# io-board-b-c.net
KiCad netlist of a schematic drawn in EAGLE
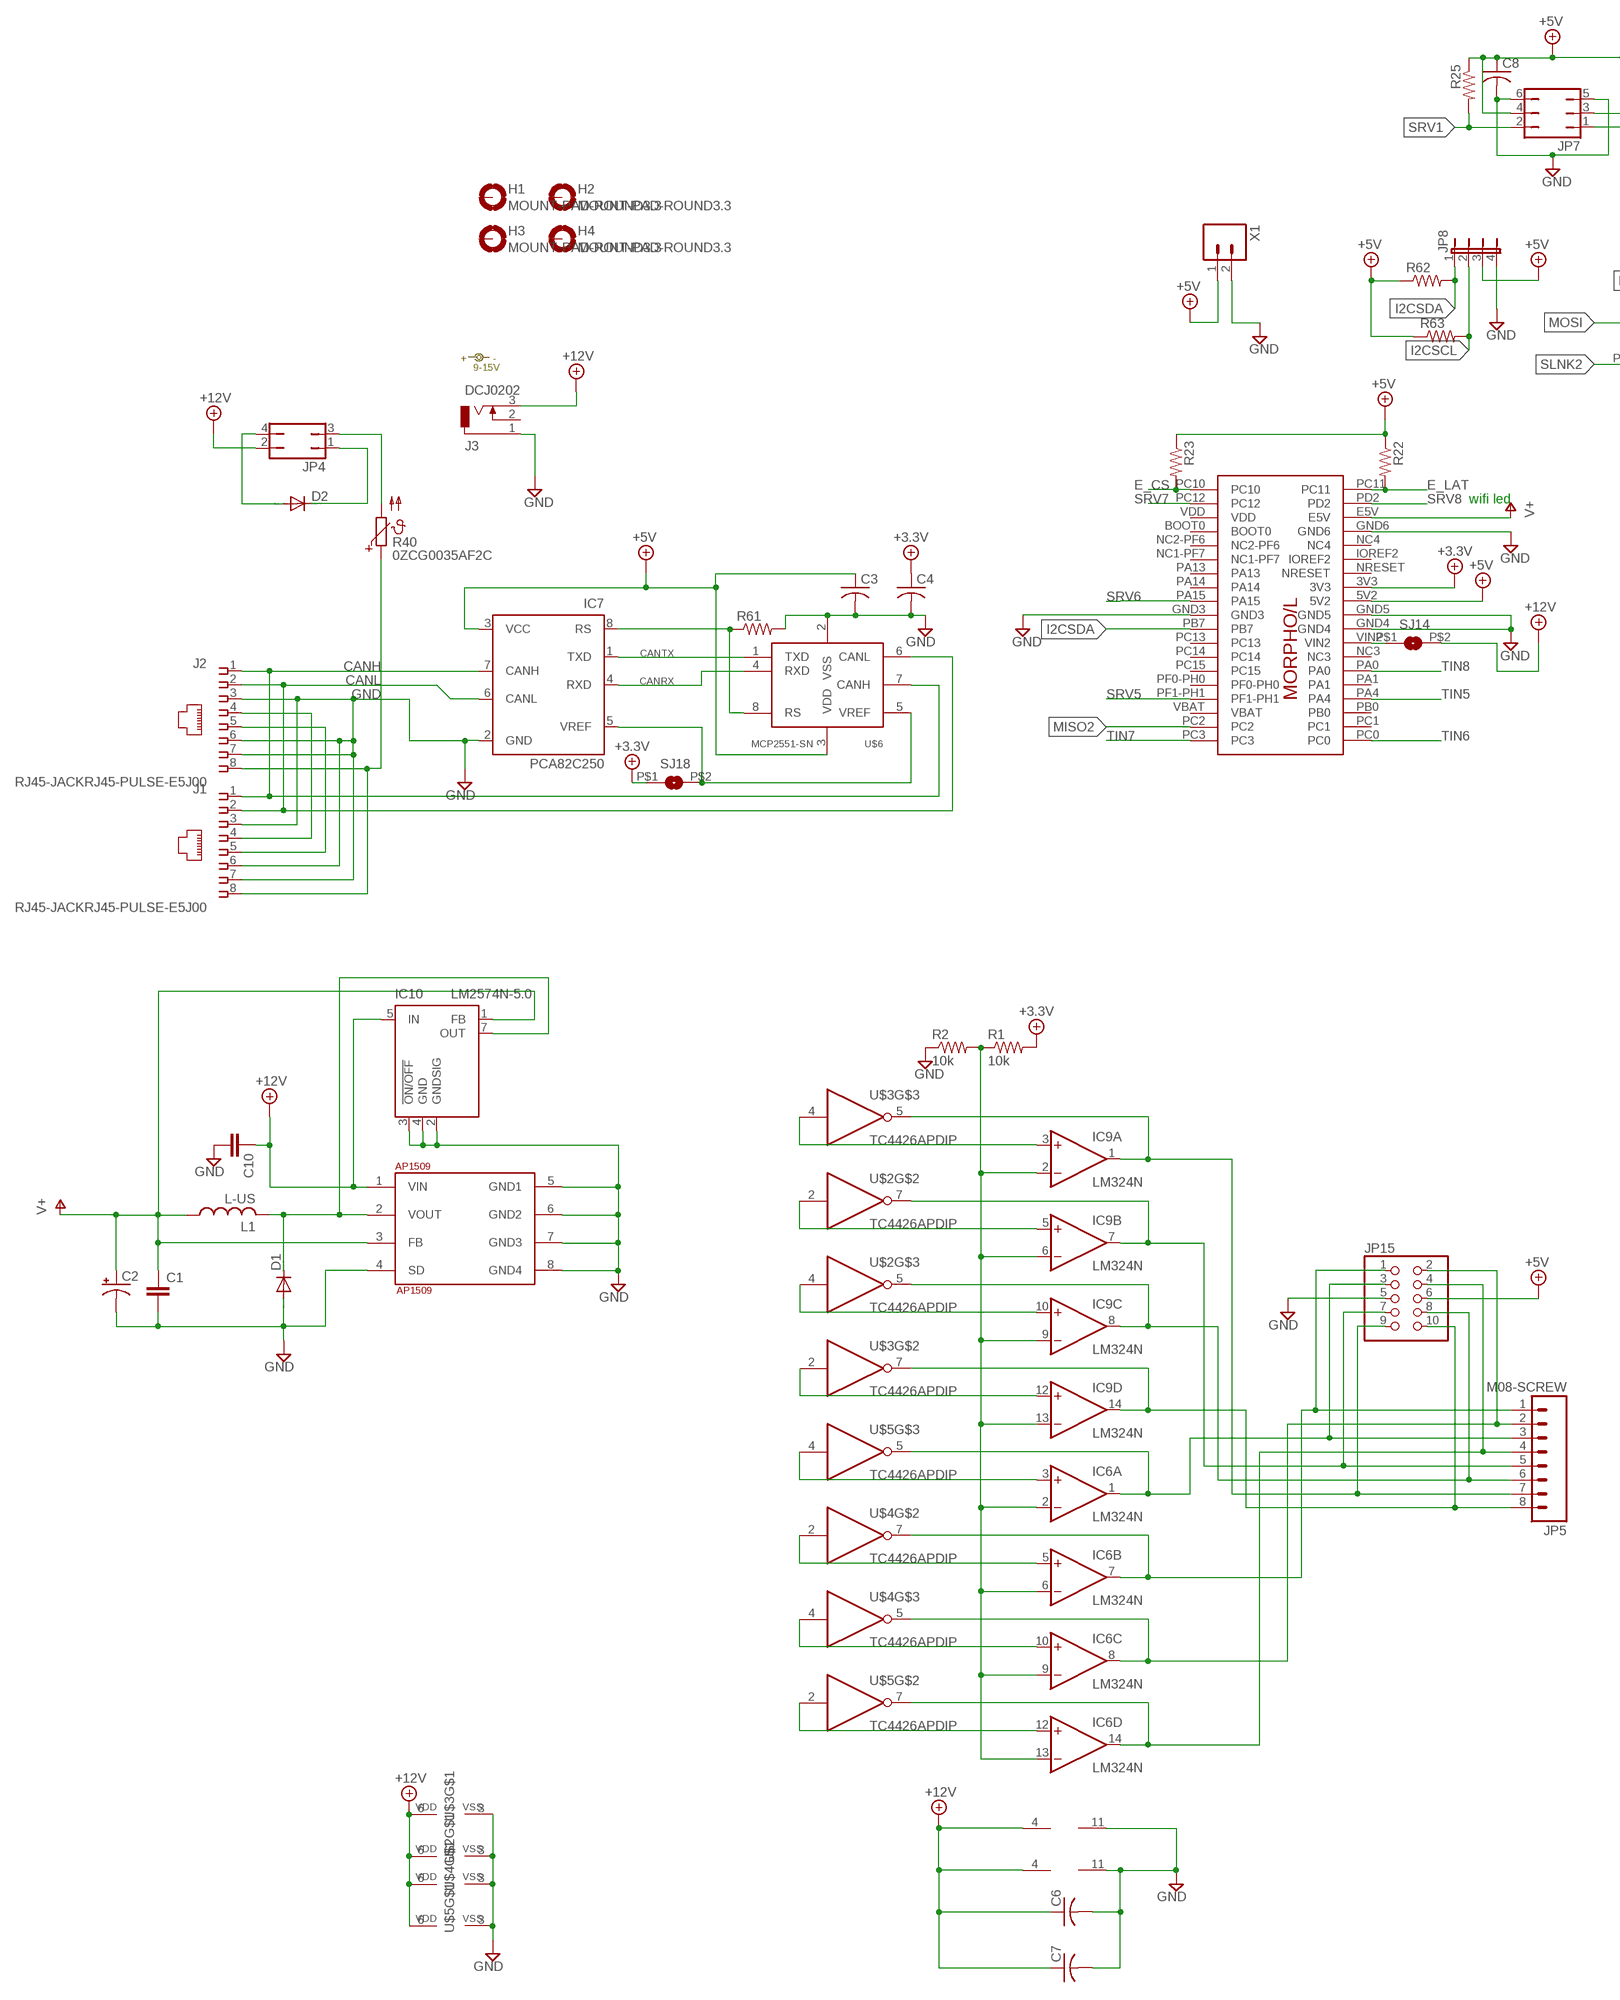
[diagram p0: schematic, sheet 1, part 1 of 2]
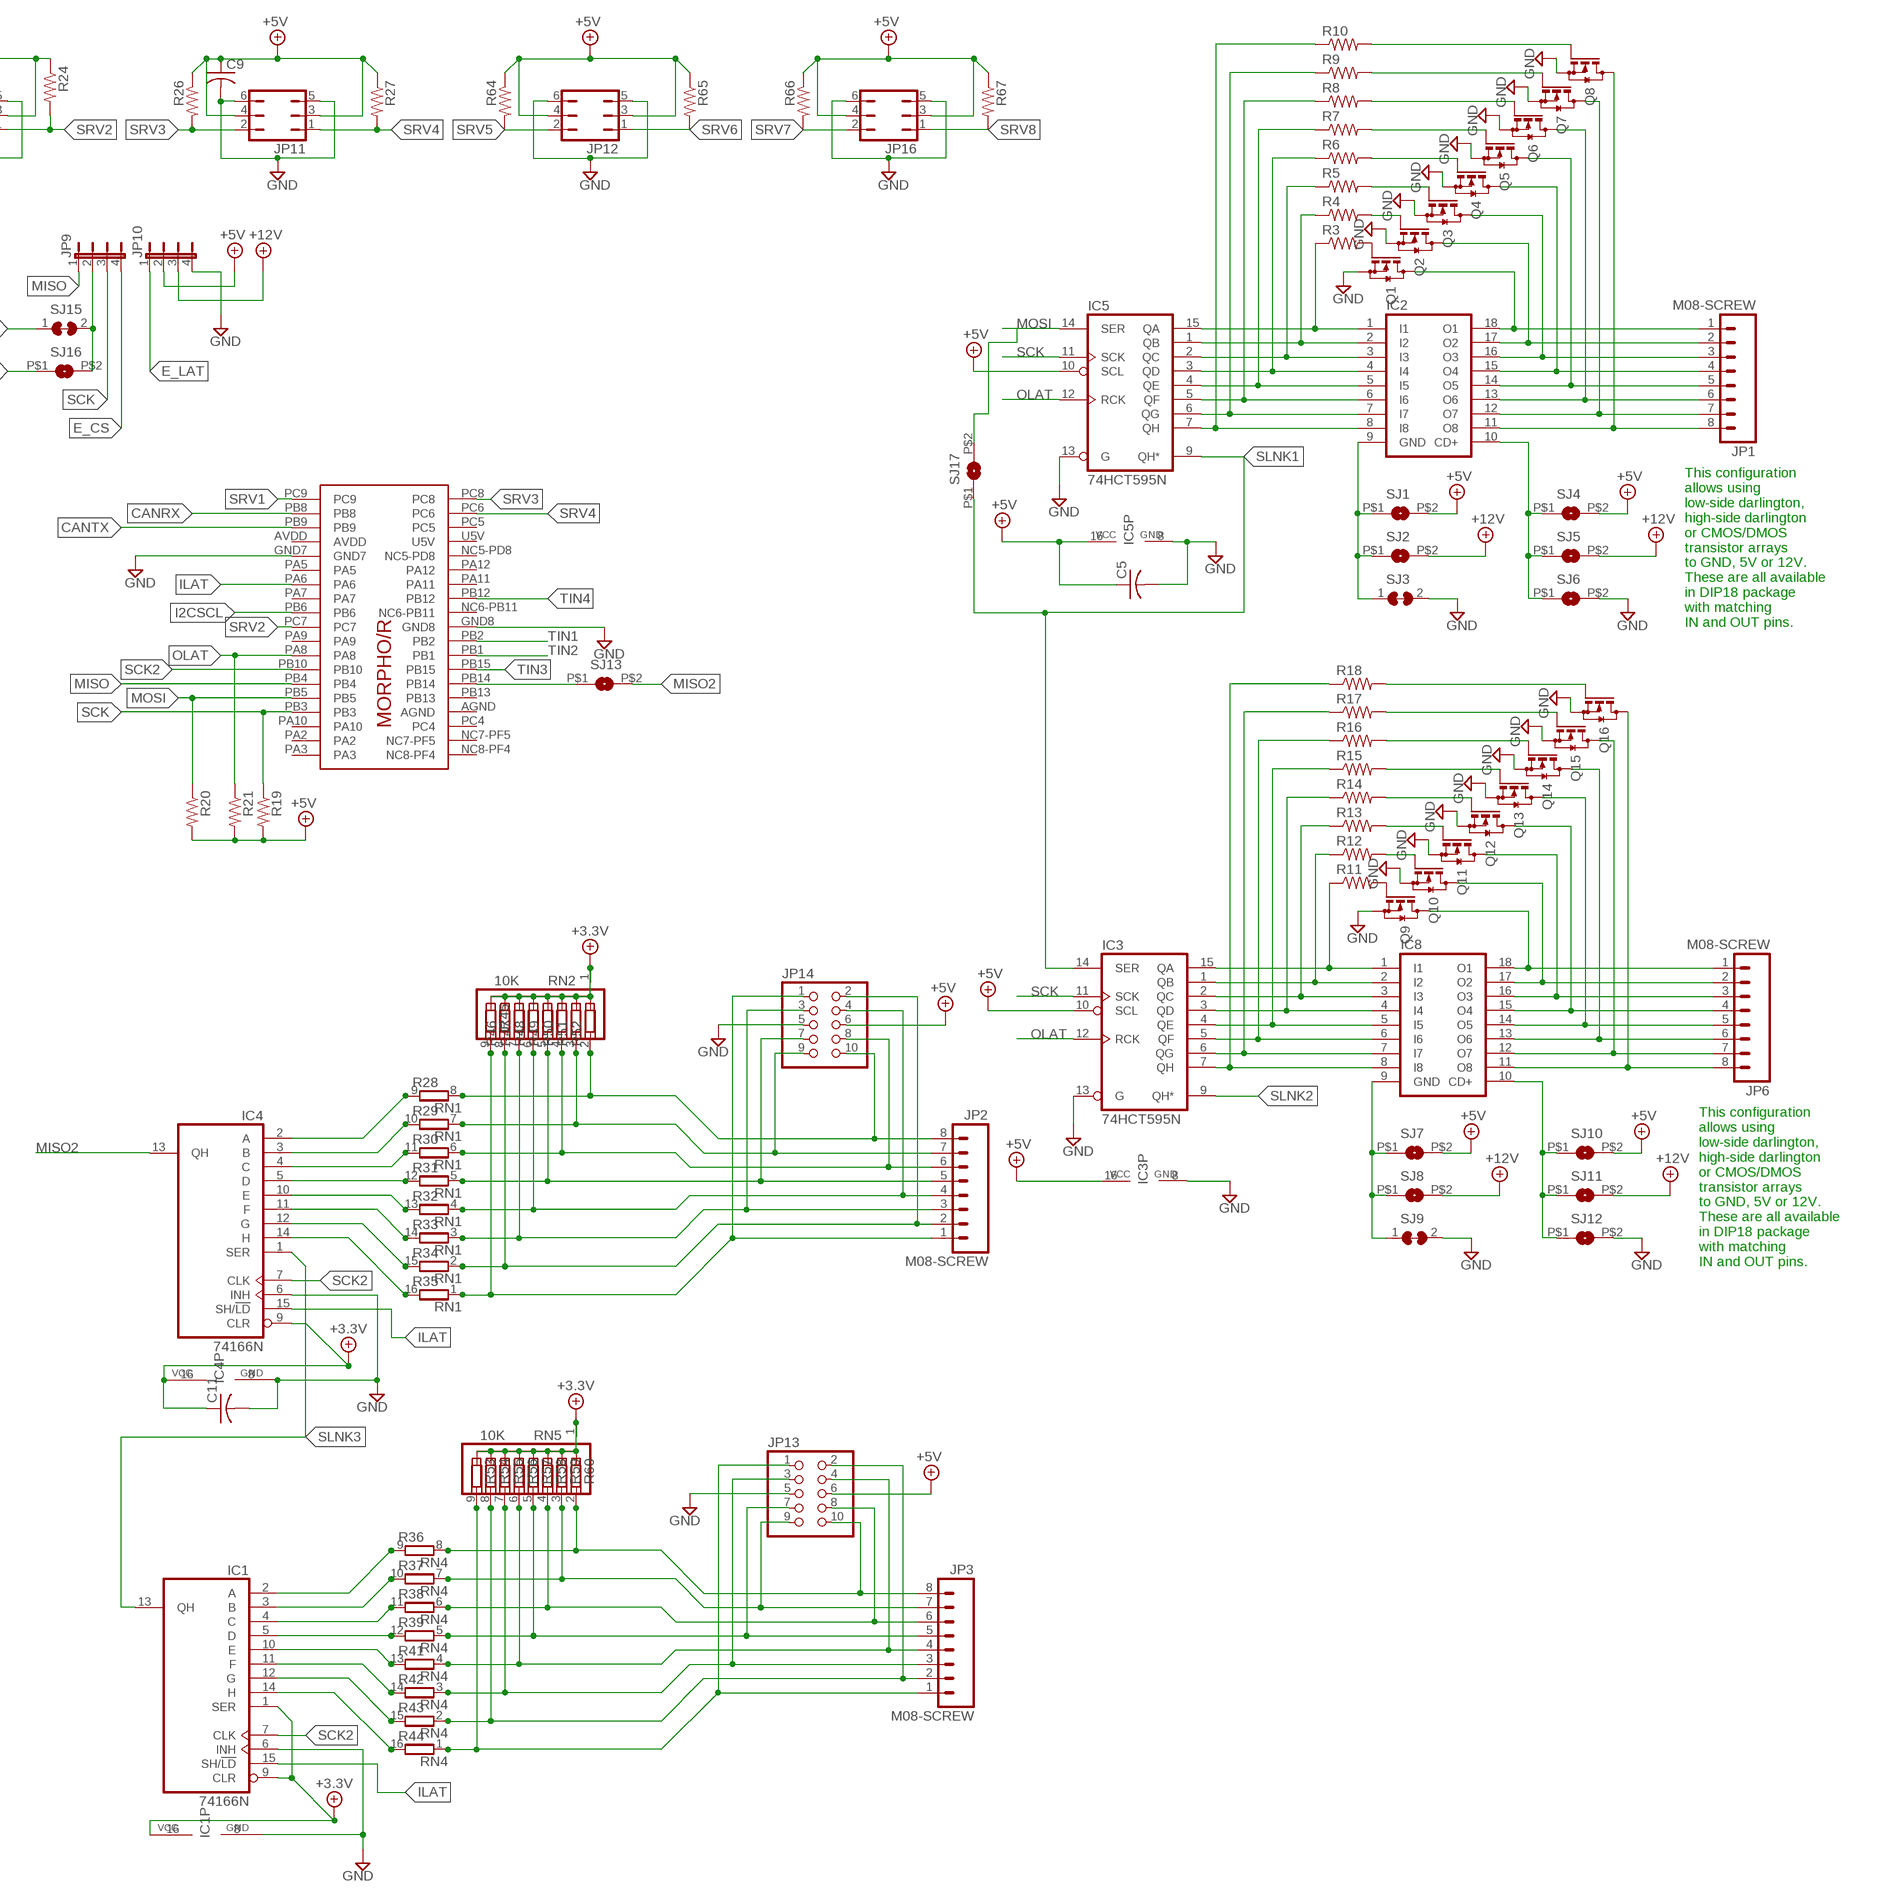
[diagram p1: schematic, sheet 1, part 2 of 2]

(export (version "E")
  (design (tool "Eeschema 10.0.6"))
  (components
    (comp (ref "+12V")
      (value "9-15V")
      (footprint "eagle-import:POWER_USAGE")
      (libsource (lib "eagle-import") (part "DOC-POWER_LABEL"))
    )
    (comp (ref "AP1509")
      (value "AP1509")
      (footprint "eagle-import:SO-08")
      (libsource (lib "eagle-import") (part "AP1509"))
    )
    (comp (ref "C1")
      (value "C-EUC1206")
      (footprint "eagle-import:C1206")
      (libsource (lib "eagle-import") (part "C-EUC1206"))
    )
    (comp (ref "C2")
      (value "CPOL-USE2.5-5")
      (footprint "eagle-import:E2,5-5")
      (libsource (lib "eagle-import") (part "CPOL-USE2.5-5"))
    )
    (comp (ref "C3")
      (value "C-USC0805")
      (footprint "eagle-import:C0805")
      (libsource (lib "eagle-import") (part "C-USC0805"))
    )
    (comp (ref "C4")
      (value "C-USC0805")
      (footprint "eagle-import:C0805")
      (libsource (lib "eagle-import") (part "C-USC0805"))
    )
    (comp (ref "C5")
      (value "C-USC0805")
      (footprint "eagle-import:C0805")
      (libsource (lib "eagle-import") (part "C-USC0805"))
    )
    (comp (ref "C6")
      (value "C-USC1206")
      (footprint "eagle-import:C1206")
      (libsource (lib "eagle-import") (part "C-USC1206"))
    )
    (comp (ref "C7")
      (value "C-USC1206")
      (footprint "eagle-import:C1206")
      (libsource (lib "eagle-import") (part "C-USC1206"))
    )
    (comp (ref "C8")
      (value "C-USC1206")
      (footprint "eagle-import:C1206")
      (libsource (lib "eagle-import") (part "C-USC1206"))
    )
    (comp (ref "C9")
      (value "C-USC1206")
      (footprint "eagle-import:C1206")
      (libsource (lib "eagle-import") (part "C-USC1206"))
    )
    (comp (ref "C10")
      (value "C-EUC1206")
      (footprint "eagle-import:C1206")
      (libsource (lib "eagle-import") (part "C-EUC1206"))
    )
    (comp (ref "C11")
      (value "C-USC0805")
      (footprint "eagle-import:C0805")
      (libsource (lib "eagle-import") (part "C-USC0805"))
    )
    (comp (ref "D1")
      (value "DIODE-DO41-7.6")
      (footprint "eagle-import:DO41-7.6")
      (libsource (lib "eagle-import") (part "DIODE-DO41-7.6"))
    )
    (comp (ref "D2")
      (value "DIODE-DO41-7.6")
      (footprint "eagle-import:DO41-7.6")
      (libsource (lib "eagle-import") (part "DIODE-DO41-7.6"))
    )
    (comp (ref "H1")
      (value "MOUNT-PAD-ROUND3.3")
      (footprint "eagle-import:3,3-PAD")
      (libsource (lib "eagle-import") (part "MOUNT-PAD-ROUND3.3"))
    )
    (comp (ref "H2")
      (value "MOUNT-PAD-ROUND3.3")
      (footprint "eagle-import:3,3-PAD")
      (libsource (lib "eagle-import") (part "MOUNT-PAD-ROUND3.3"))
    )
    (comp (ref "H3")
      (value "MOUNT-PAD-ROUND3.3")
      (footprint "eagle-import:3,3-PAD")
      (libsource (lib "eagle-import") (part "MOUNT-PAD-ROUND3.3"))
    )
    (comp (ref "H4")
      (value "MOUNT-PAD-ROUND3.3")
      (footprint "eagle-import:3,3-PAD")
      (libsource (lib "eagle-import") (part "MOUNT-PAD-ROUND3.3"))
    )
    (comp (ref "IC1")
      (value "74166N")
      (footprint "eagle-import:DIL16")
      (libsource (lib "eagle-import") (part "74166N"))
    )
    (comp (ref "IC2")
      (value "ULN2803A")
      (footprint "eagle-import:DIL18-THIN")
      (libsource (lib "eagle-import") (part "ULN2803A"))
    )
    (comp (ref "IC3")
      (value "74HCT595N")
      (footprint "eagle-import:DIL16")
      (libsource (lib "eagle-import") (part "74595NHCT"))
    )
    (comp (ref "IC4")
      (value "74166N")
      (footprint "eagle-import:DIL16")
      (libsource (lib "eagle-import") (part "74166N"))
    )
    (comp (ref "IC5")
      (value "74HCT595N")
      (footprint "eagle-import:DIL16")
      (libsource (lib "eagle-import") (part "74595NHCT"))
    )
    (comp (ref "IC6")
      (value "LM324N")
      (footprint "eagle-import:DIL14")
      (libsource (lib "eagle-import") (part "LM324N"))
    )
    (comp (ref "IC7")
      (value "PCA82C250")
      (footprint "eagle-import:DIL08")
      (libsource (lib "eagle-import") (part "PCA82C250"))
    )
    (comp (ref "IC8")
      (value "ULN2803A")
      (footprint "eagle-import:DIL18-THIN")
      (libsource (lib "eagle-import") (part "ULN2803A"))
    )
    (comp (ref "IC9")
      (value "LM324N")
      (footprint "eagle-import:DIL14")
      (libsource (lib "eagle-import") (part "LM324N"))
    )
    (comp (ref "IC10")
      (value "LM2574N-5.0")
      (footprint "eagle-import:DIL08")
      (libsource (lib "eagle-import") (part "LM2574?-N5.0"))
    )
    (comp (ref "J1")
      (value "RJ45-JACKRJ45-PULSE-E5J00")
      (footprint "eagle-import:RJ45-PULSE-E5J88")
      (libsource (lib "eagle-import") (part "RJ45-JACKRJ45-PULSE-E5J00"))
    )
    (comp (ref "J2")
      (value "RJ45-JACKRJ45-PULSE-E5J00")
      (footprint "eagle-import:RJ45-PULSE-E5J88")
      (libsource (lib "eagle-import") (part "RJ45-JACKRJ45-PULSE-E5J00"))
    )
    (comp (ref "J3")
      (value "DCJ0202")
      (footprint "eagle-import:DCJ0202")
      (libsource (lib "eagle-import") (part "DCJ0202"))
    )
    (comp (ref "JP1")
      (value "M08-SCREW")
      (footprint "eagle-import:1X08_TERMINAL")
      (libsource (lib "eagle-import") (part "M08-SCREW"))
    )
    (comp (ref "JP2")
      (value "M08-SCREW")
      (footprint "eagle-import:1X08_TERMINAL")
      (libsource (lib "eagle-import") (part "M08-SCREW"))
    )
    (comp (ref "JP3")
      (value "M08-SCREW")
      (footprint "eagle-import:1X08_TERMINAL")
      (libsource (lib "eagle-import") (part "M08-SCREW"))
    )
    (comp (ref "JP4")
      (value "JP2Q")
      (footprint "eagle-import:JP2Q")
      (libsource (lib "eagle-import") (part "JP2Q"))
    )
    (comp (ref "JP5")
      (value "M08-SCREW")
      (footprint "eagle-import:1X08_TERMINAL")
      (libsource (lib "eagle-import") (part "M08-SCREW"))
    )
    (comp (ref "JP6")
      (value "M08-SCREW")
      (footprint "eagle-import:1X08_TERMINAL")
      (libsource (lib "eagle-import") (part "M08-SCREW"))
    )
    (comp (ref "JP7")
      (value "JP3Q")
      (footprint "eagle-import:JP3Q")
      (libsource (lib "eagle-import") (part "JP3Q"))
    )
    (comp (ref "JP8")
      (value "JP4-FLAT")
      (footprint "eagle-import:JP4F")
      (libsource (lib "eagle-import") (part "JP4-FLAT"))
    )
    (comp (ref "JP9")
      (value "JP4-FLAT")
      (footprint "eagle-import:JP4F")
      (libsource (lib "eagle-import") (part "JP4-FLAT"))
    )
    (comp (ref "JP10")
      (value "JP4-FLAT")
      (footprint "eagle-import:JP4F")
      (libsource (lib "eagle-import") (part "JP4-FLAT"))
    )
    (comp (ref "JP11")
      (value "JP3Q")
      (footprint "eagle-import:JP3Q")
      (libsource (lib "eagle-import") (part "JP3Q"))
    )
    (comp (ref "JP12")
      (value "JP3Q")
      (footprint "eagle-import:JP3Q")
      (libsource (lib "eagle-import") (part "JP3Q"))
    )
    (comp (ref "JP13")
      (value "PINHD-2X5CN")
      (footprint "eagle-import:CON10M")
      (libsource (lib "eagle-import") (part "PINHD-2X5CN"))
    )
    (comp (ref "JP14")
      (value "PINHD-2X5CN")
      (footprint "eagle-import:CON10M")
      (libsource (lib "eagle-import") (part "PINHD-2X5CN"))
    )
    (comp (ref "JP15")
      (value "PINHD-2X5CN")
      (footprint "eagle-import:CON10M")
      (libsource (lib "eagle-import") (part "PINHD-2X5CN"))
    )
    (comp (ref "JP16")
      (value "JP3Q")
      (footprint "eagle-import:JP3Q")
      (libsource (lib "eagle-import") (part "JP3Q"))
    )
    (comp (ref "L1")
      (value "L-US")
      (footprint "eagle-import:L5-8,5")
      (libsource (lib "eagle-import") (part "L-US"))
    )
    (comp (ref "Q1")
      (value "BSS123")
      (footprint "eagle-import:SOT23")
      (libsource (lib "eagle-import") (part "BSS123"))
    )
    (comp (ref "Q2")
      (value "BSS123")
      (footprint "eagle-import:SOT23")
      (libsource (lib "eagle-import") (part "BSS123"))
    )
    (comp (ref "Q3")
      (value "BSS123")
      (footprint "eagle-import:SOT23")
      (libsource (lib "eagle-import") (part "BSS123"))
    )
    (comp (ref "Q4")
      (value "BSS123")
      (footprint "eagle-import:SOT23")
      (libsource (lib "eagle-import") (part "BSS123"))
    )
    (comp (ref "Q5")
      (value "BSS123")
      (footprint "eagle-import:SOT23")
      (libsource (lib "eagle-import") (part "BSS123"))
    )
    (comp (ref "Q6")
      (value "BSS123")
      (footprint "eagle-import:SOT23")
      (libsource (lib "eagle-import") (part "BSS123"))
    )
    (comp (ref "Q7")
      (value "BSS123")
      (footprint "eagle-import:SOT23")
      (libsource (lib "eagle-import") (part "BSS123"))
    )
    (comp (ref "Q8")
      (value "BSS123")
      (footprint "eagle-import:SOT23")
      (libsource (lib "eagle-import") (part "BSS123"))
    )
    (comp (ref "Q9")
      (value "BSS123")
      (footprint "eagle-import:SOT23")
      (libsource (lib "eagle-import") (part "BSS123"))
    )
    (comp (ref "Q10")
      (value "BSS123")
      (footprint "eagle-import:SOT23")
      (libsource (lib "eagle-import") (part "BSS123"))
    )
    (comp (ref "Q11")
      (value "BSS123")
      (footprint "eagle-import:SOT23")
      (libsource (lib "eagle-import") (part "BSS123"))
    )
    (comp (ref "Q12")
      (value "BSS123")
      (footprint "eagle-import:SOT23")
      (libsource (lib "eagle-import") (part "BSS123"))
    )
    (comp (ref "Q13")
      (value "BSS123")
      (footprint "eagle-import:SOT23")
      (libsource (lib "eagle-import") (part "BSS123"))
    )
    (comp (ref "Q14")
      (value "BSS123")
      (footprint "eagle-import:SOT23")
      (libsource (lib "eagle-import") (part "BSS123"))
    )
    (comp (ref "Q15")
      (value "BSS123")
      (footprint "eagle-import:SOT23")
      (libsource (lib "eagle-import") (part "BSS123"))
    )
    (comp (ref "Q16")
      (value "BSS123")
      (footprint "eagle-import:SOT23")
      (libsource (lib "eagle-import") (part "BSS123"))
    )
    (comp (ref "R1")
      (value "10k")
      (footprint "eagle-import:R0805")
      (libsource (lib "eagle-import") (part "R-US_R0805"))
    )
    (comp (ref "R2")
      (value "10k")
      (footprint "eagle-import:R0805")
      (libsource (lib "eagle-import") (part "R-US_R0805"))
    )
    (comp (ref "R3")
      (value "R-US_R0603")
      (footprint "eagle-import:R0603")
      (libsource (lib "eagle-import") (part "R-US_R0603"))
    )
    (comp (ref "R4")
      (value "R-US_R0603")
      (footprint "eagle-import:R0603")
      (libsource (lib "eagle-import") (part "R-US_R0603"))
    )
    (comp (ref "R5")
      (value "R-US_R0603")
      (footprint "eagle-import:R0603")
      (libsource (lib "eagle-import") (part "R-US_R0603"))
    )
    (comp (ref "R6")
      (value "R-US_R0603")
      (footprint "eagle-import:R0603")
      (libsource (lib "eagle-import") (part "R-US_R0603"))
    )
    (comp (ref "R7")
      (value "R-US_R0603")
      (footprint "eagle-import:R0603")
      (libsource (lib "eagle-import") (part "R-US_R0603"))
    )
    (comp (ref "R8")
      (value "R-US_R0603")
      (footprint "eagle-import:R0603")
      (libsource (lib "eagle-import") (part "R-US_R0603"))
    )
    (comp (ref "R9")
      (value "R-US_R0603")
      (footprint "eagle-import:R0603")
      (libsource (lib "eagle-import") (part "R-US_R0603"))
    )
    (comp (ref "R10")
      (value "R-US_R0603")
      (footprint "eagle-import:R0603")
      (libsource (lib "eagle-import") (part "R-US_R0603"))
    )
    (comp (ref "R11")
      (value "R-US_R0603")
      (footprint "eagle-import:R0603")
      (libsource (lib "eagle-import") (part "R-US_R0603"))
    )
    (comp (ref "R12")
      (value "R-US_R0603")
      (footprint "eagle-import:R0603")
      (libsource (lib "eagle-import") (part "R-US_R0603"))
    )
    (comp (ref "R13")
      (value "R-US_R0603")
      (footprint "eagle-import:R0603")
      (libsource (lib "eagle-import") (part "R-US_R0603"))
    )
    (comp (ref "R14")
      (value "R-US_R0603")
      (footprint "eagle-import:R0603")
      (libsource (lib "eagle-import") (part "R-US_R0603"))
    )
    (comp (ref "R15")
      (value "R-US_R0603")
      (footprint "eagle-import:R0603")
      (libsource (lib "eagle-import") (part "R-US_R0603"))
    )
    (comp (ref "R16")
      (value "R-US_R0603")
      (footprint "eagle-import:R0603")
      (libsource (lib "eagle-import") (part "R-US_R0603"))
    )
    (comp (ref "R17")
      (value "R-US_R0603")
      (footprint "eagle-import:R0603")
      (libsource (lib "eagle-import") (part "R-US_R0603"))
    )
    (comp (ref "R18")
      (value "R-US_R0603")
      (footprint "eagle-import:R0603")
      (libsource (lib "eagle-import") (part "R-US_R0603"))
    )
    (comp (ref "R19")
      (value "R-US_R0805")
      (footprint "eagle-import:R0805")
      (libsource (lib "eagle-import") (part "rcl_334_R-US_R0805"))
    )
    (comp (ref "R20")
      (value "R-US_R0805")
      (footprint "eagle-import:R0805")
      (libsource (lib "eagle-import") (part "rcl_334_R-US_R0805"))
    )
    (comp (ref "R21")
      (value "R-US_R0805")
      (footprint "eagle-import:R0805")
      (libsource (lib "eagle-import") (part "rcl_334_R-US_R0805"))
    )
    (comp (ref "R22")
      (value "R-US_R0805")
      (footprint "eagle-import:R0805")
      (libsource (lib "eagle-import") (part "rcl_334_R-US_R0805"))
    )
    (comp (ref "R23")
      (value "R-US_R0805")
      (footprint "eagle-import:R0805")
      (libsource (lib "eagle-import") (part "rcl_334_R-US_R0805"))
    )
    (comp (ref "R24")
      (value "R-US_R0805")
      (footprint "eagle-import:R0805")
      (libsource (lib "eagle-import") (part "rcl_334_R-US_R0805"))
    )
    (comp (ref "R25")
      (value "R-US_R0805")
      (footprint "eagle-import:R0805")
      (libsource (lib "eagle-import") (part "rcl_334_R-US_R0805"))
    )
    (comp (ref "R26")
      (value "R-US_R0805")
      (footprint "eagle-import:R0805")
      (libsource (lib "eagle-import") (part "rcl_334_R-US_R0805"))
    )
    (comp (ref "R27")
      (value "R-US_R0805")
      (footprint "eagle-import:R0805")
      (libsource (lib "eagle-import") (part "rcl_334_R-US_R0805"))
    )
    (comp (ref "R28")
      (value "R-EU_R0603")
      (footprint "eagle-import:R0603")
      (libsource (lib "eagle-import") (part "R-EU_R0603"))
    )
    (comp (ref "R29")
      (value "R-EU_R0603")
      (footprint "eagle-import:R0603")
      (libsource (lib "eagle-import") (part "R-EU_R0603"))
    )
    (comp (ref "R30")
      (value "R-EU_R0603")
      (footprint "eagle-import:R0603")
      (libsource (lib "eagle-import") (part "R-EU_R0603"))
    )
    (comp (ref "R31")
      (value "R-EU_R0603")
      (footprint "eagle-import:R0603")
      (libsource (lib "eagle-import") (part "R-EU_R0603"))
    )
    (comp (ref "R32")
      (value "R-EU_R0603")
      (footprint "eagle-import:R0603")
      (libsource (lib "eagle-import") (part "R-EU_R0603"))
    )
    (comp (ref "R33")
      (value "R-EU_R0603")
      (footprint "eagle-import:R0603")
      (libsource (lib "eagle-import") (part "R-EU_R0603"))
    )
    (comp (ref "R34")
      (value "R-EU_R0603")
      (footprint "eagle-import:R0603")
      (libsource (lib "eagle-import") (part "R-EU_R0603"))
    )
    (comp (ref "R35")
      (value "R-EU_R0603")
      (footprint "eagle-import:R0603")
      (libsource (lib "eagle-import") (part "R-EU_R0603"))
    )
    (comp (ref "R36")
      (value "R-EU_R0603")
      (footprint "eagle-import:R0603")
      (libsource (lib "eagle-import") (part "R-EU_R0603"))
    )
    (comp (ref "R37")
      (value "R-EU_R0603")
      (footprint "eagle-import:R0603")
      (libsource (lib "eagle-import") (part "R-EU_R0603"))
    )
    (comp (ref "R38")
      (value "R-EU_R0603")
      (footprint "eagle-import:R0603")
      (libsource (lib "eagle-import") (part "R-EU_R0603"))
    )
    (comp (ref "R39")
      (value "R-EU_R0603")
      (footprint "eagle-import:R0603")
      (libsource (lib "eagle-import") (part "R-EU_R0603"))
    )
    (comp (ref "R40")
      (value "0ZCG0035AF2C")
      (footprint "eagle-import:PTC1812")
      (libsource (lib "eagle-import") (part "PTC_1812"))
    )
    (comp (ref "R41")
      (value "R-EU_R0603")
      (footprint "eagle-import:R0603")
      (libsource (lib "eagle-import") (part "R-EU_R0603"))
    )
    (comp (ref "R42")
      (value "R-EU_R0603")
      (footprint "eagle-import:R0603")
      (libsource (lib "eagle-import") (part "R-EU_R0603"))
    )
    (comp (ref "R43")
      (value "R-EU_R0603")
      (footprint "eagle-import:R0603")
      (libsource (lib "eagle-import") (part "R-EU_R0603"))
    )
    (comp (ref "R44")
      (value "R-EU_R0603")
      (footprint "eagle-import:R0603")
      (libsource (lib "eagle-import") (part "R-EU_R0603"))
    )
    (comp (ref "R45")
      (value "R-EU_R0603")
      (footprint "eagle-import:R0603")
      (libsource (lib "eagle-import") (part "R-EU_R0603"))
    )
    (comp (ref "R46")
      (value "R-EU_R0603")
      (footprint "eagle-import:R0603")
      (libsource (lib "eagle-import") (part "R-EU_R0603"))
    )
    (comp (ref "R47")
      (value "R-EU_R0603")
      (footprint "eagle-import:R0603")
      (libsource (lib "eagle-import") (part "R-EU_R0603"))
    )
    (comp (ref "R48")
      (value "R-EU_R0603")
      (footprint "eagle-import:R0603")
      (libsource (lib "eagle-import") (part "R-EU_R0603"))
    )
    (comp (ref "R49")
      (value "R-EU_R0603")
      (footprint "eagle-import:R0603")
      (libsource (lib "eagle-import") (part "R-EU_R0603"))
    )
    (comp (ref "R50")
      (value "R-EU_R0603")
      (footprint "eagle-import:R0603")
      (libsource (lib "eagle-import") (part "R-EU_R0603"))
    )
    (comp (ref "R51")
      (value "R-EU_R0603")
      (footprint "eagle-import:R0603")
      (libsource (lib "eagle-import") (part "R-EU_R0603"))
    )
    (comp (ref "R52")
      (value "R-EU_R0603")
      (footprint "eagle-import:R0603")
      (libsource (lib "eagle-import") (part "R-EU_R0603"))
    )
    (comp (ref "R53")
      (value "R-EU_R0603")
      (footprint "eagle-import:R0603")
      (libsource (lib "eagle-import") (part "R-EU_R0603"))
    )
    (comp (ref "R54")
      (value "R-EU_R0603")
      (footprint "eagle-import:R0603")
      (libsource (lib "eagle-import") (part "R-EU_R0603"))
    )
    (comp (ref "R55")
      (value "R-EU_R0603")
      (footprint "eagle-import:R0603")
      (libsource (lib "eagle-import") (part "R-EU_R0603"))
    )
    (comp (ref "R56")
      (value "R-EU_R0603")
      (footprint "eagle-import:R0603")
      (libsource (lib "eagle-import") (part "R-EU_R0603"))
    )
    (comp (ref "R57")
      (value "R-EU_R0603")
      (footprint "eagle-import:R0603")
      (libsource (lib "eagle-import") (part "R-EU_R0603"))
    )
    (comp (ref "R58")
      (value "R-EU_R0603")
      (footprint "eagle-import:R0603")
      (libsource (lib "eagle-import") (part "R-EU_R0603"))
    )
    (comp (ref "R59")
      (value "R-EU_R0603")
      (footprint "eagle-import:R0603")
      (libsource (lib "eagle-import") (part "R-EU_R0603"))
    )
    (comp (ref "R60")
      (value "R-EU_R0603")
      (footprint "eagle-import:R0603")
      (libsource (lib "eagle-import") (part "R-EU_R0603"))
    )
    (comp (ref "R61")
      (value "R-US_R0805")
      (footprint "eagle-import:R0805")
      (libsource (lib "eagle-import") (part "rcl_334_R-US_R0805"))
    )
    (comp (ref "R62")
      (value "R-US_R0805")
      (footprint "eagle-import:R0805")
      (libsource (lib "eagle-import") (part "rcl_334_R-US_R0805"))
    )
    (comp (ref "R63")
      (value "R-US_R0805")
      (footprint "eagle-import:R0805")
      (libsource (lib "eagle-import") (part "rcl_334_R-US_R0805"))
    )
    (comp (ref "R64")
      (value "R-US_R0805")
      (footprint "eagle-import:R0805")
      (libsource (lib "eagle-import") (part "rcl_334_R-US_R0805"))
    )
    (comp (ref "R65")
      (value "R-US_R0805")
      (footprint "eagle-import:R0805")
      (libsource (lib "eagle-import") (part "rcl_334_R-US_R0805"))
    )
    (comp (ref "R66")
      (value "R-US_R0805")
      (footprint "eagle-import:R0805")
      (libsource (lib "eagle-import") (part "rcl_334_R-US_R0805"))
    )
    (comp (ref "R67")
      (value "R-US_R0805")
      (footprint "eagle-import:R0805")
      (libsource (lib "eagle-import") (part "rcl_334_R-US_R0805"))
    )
    (comp (ref "RN1")
      (value "8R-P")
      (footprint "eagle-import:DIL16")
      (libsource (lib "eagle-import") (part "8R-P"))
    )
    (comp (ref "RN2")
      (value "10K")
      (footprint "eagle-import:SIL9")
      (libsource (lib "eagle-import") (part "G08R"))
    )
    (comp (ref "RN4")
      (value "8R-P")
      (footprint "eagle-import:DIL16")
      (libsource (lib "eagle-import") (part "8R-P"))
    )
    (comp (ref "RN5")
      (value "10K")
      (footprint "eagle-import:SIL9")
      (libsource (lib "eagle-import") (part "G08R"))
    )
    (comp (ref "SJ1")
      (value "SJRND2")
      (footprint "eagle-import:SJ_RND2")
      (libsource (lib "eagle-import") (part "SJRND2"))
    )
    (comp (ref "SJ2")
      (value "SJRND2")
      (footprint "eagle-import:SJ_RND2")
      (libsource (lib "eagle-import") (part "SJRND2"))
    )
    (comp (ref "SJ3")
      (value "SJ-C")
      (footprint "eagle-import:SJW-C")
      (libsource (lib "eagle-import") (part "SJ-C"))
    )
    (comp (ref "SJ4")
      (value "SJRND2")
      (footprint "eagle-import:SJ_RND2")
      (libsource (lib "eagle-import") (part "SJRND2"))
    )
    (comp (ref "SJ5")
      (value "SJRND2")
      (footprint "eagle-import:SJ_RND2")
      (libsource (lib "eagle-import") (part "SJRND2"))
    )
    (comp (ref "SJ6")
      (value "SJRND2")
      (footprint "eagle-import:SJ_RND2")
      (libsource (lib "eagle-import") (part "SJRND2"))
    )
    (comp (ref "SJ7")
      (value "SJRND2")
      (footprint "eagle-import:SJ_RND2")
      (libsource (lib "eagle-import") (part "SJRND2"))
    )
    (comp (ref "SJ8")
      (value "SJRND2")
      (footprint "eagle-import:SJ_RND2")
      (libsource (lib "eagle-import") (part "SJRND2"))
    )
    (comp (ref "SJ9")
      (value "SJ-C")
      (footprint "eagle-import:SJW-C")
      (libsource (lib "eagle-import") (part "SJ-C"))
    )
    (comp (ref "SJ10")
      (value "SJRND2")
      (footprint "eagle-import:SJ_RND2")
      (libsource (lib "eagle-import") (part "SJRND2"))
    )
    (comp (ref "SJ11")
      (value "SJRND2")
      (footprint "eagle-import:SJ_RND2")
      (libsource (lib "eagle-import") (part "SJRND2"))
    )
    (comp (ref "SJ12")
      (value "SJRND2")
      (footprint "eagle-import:SJ_RND2")
      (libsource (lib "eagle-import") (part "SJRND2"))
    )
    (comp (ref "SJ13")
      (value "SJRND2")
      (footprint "eagle-import:SJ_RND2")
      (libsource (lib "eagle-import") (part "SJRND2"))
    )
    (comp (ref "SJ14")
      (value "SJRND2")
      (footprint "eagle-import:SJ_RND2")
      (libsource (lib "eagle-import") (part "SJRND2"))
    )
    (comp (ref "SJ15")
      (value "SJ-C")
      (footprint "eagle-import:SJW-C")
      (libsource (lib "eagle-import") (part "SJ-C"))
    )
    (comp (ref "SJ16")
      (value "SJRND2")
      (footprint "eagle-import:SJ_RND2")
      (libsource (lib "eagle-import") (part "SJRND2"))
    )
    (comp (ref "SJ17")
      (value "SJRND2")
      (footprint "eagle-import:SJ_RND2")
      (libsource (lib "eagle-import") (part "SJRND2"))
    )
    (comp (ref "SJ18")
      (value "SJRND2")
      (footprint "eagle-import:SJ_RND2")
      (libsource (lib "eagle-import") (part "SJRND2"))
    )
    (comp (ref "U$1")
      (value "NUCLEO_64_GENERIC")
      (footprint "eagle-import:NUCLEO_BRD_BASE64")
      (libsource (lib "eagle-import") (part "NUCLEO_64_GENERIC"))
    )
    (comp (ref "U$2")
      (value "TC4426APDIP")
      (footprint "eagle-import:DIL08-LONG")
      (libsource (lib "eagle-import") (part "TC4426APDIP"))
    )
    (comp (ref "U$3")
      (value "TC4426APDIP")
      (footprint "eagle-import:DIL08-LONG")
      (libsource (lib "eagle-import") (part "TC4426APDIP"))
    )
    (comp (ref "U$4")
      (value "TC4426APDIP")
      (footprint "eagle-import:DIL08-LONG")
      (libsource (lib "eagle-import") (part "TC4426APDIP"))
    )
    (comp (ref "U$5")
      (value "TC4426APDIP")
      (footprint "eagle-import:DIL08-LONG")
      (libsource (lib "eagle-import") (part "TC4426APDIP"))
    )
    (comp (ref "U$6")
      (value "MCP2551-SN")
      (footprint "eagle-import:SO-08")
      (libsource (lib "eagle-import") (part "MCP2551-SN"))
    )
    (comp (ref "X1")
      (value "CONNECTOR-M023.5MM-LOCK")
      (footprint "eagle-import:SCREWTERMINAL-3.5MM-2_LOCK")
      (libsource (lib "eagle-import") (part "CONNECTOR-M023.5MM-LOCK"))
    )
  )
  (nets
    (net (code "1") (name "+3.3V") (class "Default")
      (node (ref "C11") (pin "1") (pinfunction "1_1") (pintype "passive"))
      (node (ref "C4") (pin "1") (pinfunction "1_1") (pintype "passive"))
      (node (ref "IC1") (pin "1") (pinfunction "SER_1") (pintype "input"))
      (node (ref "IC1") (pin "16") (pinfunction "VCC_16") (pintype "power_in"))
      (node (ref "IC1") (pin "9") (pinfunction "CLR_9") (pintype "input"))
      (node (ref "IC4") (pin "16") (pinfunction "VCC_16") (pintype "power_in"))
      (node (ref "IC4") (pin "9") (pinfunction "CLR_9") (pintype "input"))
      (node (ref "R1") (pin "2") (pinfunction "2_2") (pintype "passive"))
      (node (ref "R45") (pin "1") (pinfunction "1_1") (pintype "passive"))
      (node (ref "R46") (pin "2") (pinfunction "2_2") (pintype "passive"))
      (node (ref "R47") (pin "2") (pinfunction "2_2") (pintype "passive"))
      (node (ref "R48") (pin "2") (pinfunction "2_2") (pintype "passive"))
      (node (ref "R49") (pin "2") (pinfunction "2_2") (pintype "passive"))
      (node (ref "R50") (pin "2") (pinfunction "2_2") (pintype "passive"))
      (node (ref "R51") (pin "2") (pinfunction "2_2") (pintype "passive"))
      (node (ref "R52") (pin "2") (pinfunction "2_2") (pintype "passive"))
      (node (ref "R53") (pin "1") (pinfunction "1_1") (pintype "passive"))
      (node (ref "R54") (pin "1") (pinfunction "1_1") (pintype "passive"))
      (node (ref "R55") (pin "1") (pinfunction "1_1") (pintype "passive"))
      (node (ref "R56") (pin "1") (pinfunction "1_1") (pintype "passive"))
      (node (ref "R57") (pin "1") (pinfunction "1_1") (pintype "passive"))
      (node (ref "R58") (pin "1") (pinfunction "1_1") (pintype "passive"))
      (node (ref "R59") (pin "1") (pinfunction "1_1") (pintype "passive"))
      (node (ref "R60") (pin "1") (pinfunction "1_1") (pintype "passive"))
      (node (ref "RN2") (pin "1") (pinfunction "1_1") (pintype "passive"))
      (node (ref "RN5") (pin "1") (pinfunction "1_1") (pintype "passive"))
      (node (ref "SJ18") (pin "P$1") (pinfunction "1_P$1") (pintype "passive"))
      (node (ref "U$1") (pin "3V3") (pinfunction "3V3_3V3") (pintype "power_in"))
    )
    (net (code "2") (name "+5V") (class "Default")
      (node (ref "C3") (pin "1") (pinfunction "1_1") (pintype "passive"))
      (node (ref "C5") (pin "1") (pinfunction "1_1") (pintype "passive"))
      (node (ref "C8") (pin "1") (pinfunction "1_1") (pintype "passive"))
      (node (ref "C9") (pin "1") (pinfunction "1_1") (pintype "passive"))
      (node (ref "IC3") (pin "10") (pinfunction "SCL_10") (pintype "input"))
      (node (ref "IC3") (pin "16") (pinfunction "VCC_16") (pintype "power_in"))
      (node (ref "IC5") (pin "10") (pinfunction "SCL_10") (pintype "input"))
      (node (ref "IC5") (pin "16") (pinfunction "VCC_16") (pintype "power_in"))
      (node (ref "IC7") (pin "3") (pinfunction "VCC_3") (pintype "power_in"))
      (node (ref "JP10") (pin "2") (pinfunction "2_2") (pintype "passive"))
      (node (ref "JP11") (pin "3") (pinfunction "3_3") (pintype "passive"))
      (node (ref "JP11") (pin "4") (pinfunction "4_4") (pintype "passive"))
      (node (ref "JP12") (pin "3") (pinfunction "3_3") (pintype "passive"))
      (node (ref "JP12") (pin "4") (pinfunction "4_4") (pintype "passive"))
      (node (ref "JP13") (pin "6") (pinfunction "6_6") (pintype "passive"))
      (node (ref "JP14") (pin "6") (pinfunction "6_6") (pintype "passive"))
      (node (ref "JP15") (pin "6") (pinfunction "6_6") (pintype "passive"))
      (node (ref "JP16") (pin "3") (pinfunction "3_3") (pintype "passive"))
      (node (ref "JP16") (pin "4") (pinfunction "4_4") (pintype "passive"))
      (node (ref "JP7") (pin "3") (pinfunction "3_3") (pintype "passive"))
      (node (ref "JP7") (pin "4") (pinfunction "4_4") (pintype "passive"))
      (node (ref "JP8") (pin "3") (pinfunction "3_3") (pintype "passive"))
      (node (ref "R19") (pin "2") (pinfunction "2_2") (pintype "passive"))
      (node (ref "R20") (pin "2") (pinfunction "2_2") (pintype "passive"))
      (node (ref "R21") (pin "2") (pinfunction "2_2") (pintype "passive"))
      (node (ref "R22") (pin "1") (pinfunction "1_1") (pintype "passive"))
      (node (ref "R23") (pin "1") (pinfunction "1_1") (pintype "passive"))
      (node (ref "R24") (pin "1") (pinfunction "1_1") (pintype "passive"))
      (node (ref "R25") (pin "1") (pinfunction "1_1") (pintype "passive"))
      (node (ref "R26") (pin "1") (pinfunction "1_1") (pintype "passive"))
      (node (ref "R27") (pin "1") (pinfunction "1_1") (pintype "passive"))
      (node (ref "R62") (pin "1") (pinfunction "1_1") (pintype "passive"))
      (node (ref "R63") (pin "1") (pinfunction "1_1") (pintype "passive"))
      (node (ref "R64") (pin "1") (pinfunction "1_1") (pintype "passive"))
      (node (ref "R65") (pin "1") (pinfunction "1_1") (pintype "passive"))
      (node (ref "R66") (pin "1") (pinfunction "1_1") (pintype "passive"))
      (node (ref "R67") (pin "1") (pinfunction "1_1") (pintype "passive"))
      (node (ref "SJ1") (pin "P$2") (pinfunction "2_P$2") (pintype "passive"))
      (node (ref "SJ10") (pin "P$2") (pinfunction "2_P$2") (pintype "passive"))
      (node (ref "SJ4") (pin "P$2") (pinfunction "2_P$2") (pintype "passive"))
      (node (ref "SJ7") (pin "P$2") (pinfunction "2_P$2") (pintype "passive"))
      (node (ref "U$1") (pin "5V2") (pinfunction "5V2_5V2") (pintype "power_in"))
      (node (ref "U$6") (pin "3") (pinfunction "VDD_3") (pintype "power_in"))
      (node (ref "X1") (pin "1") (pinfunction "1_1") (pintype "passive"))
    )
    (net (code "3") (name "+12V") (class "Default")
      (node (ref "AP1509") (pin "1") (pinfunction "VIN_1") (pintype "bidirectional"))
      (node (ref "C10") (pin "1") (pinfunction "1_1") (pintype "passive"))
      (node (ref "C6") (pin "1") (pinfunction "1_1") (pintype "passive"))
      (node (ref "C7") (pin "1") (pinfunction "1_1") (pintype "passive"))
      (node (ref "IC10") (pin "5") (pinfunction "IN_5") (pintype "input"))
      (node (ref "IC6") (pin "4") (pinfunction "V+_4") (pintype "power_in"))
      (node (ref "IC9") (pin "4") (pinfunction "V+_4") (pintype "power_in"))
      (node (ref "J3") (pin "3") (pinfunction "3_3") (pintype "passive"))
      (node (ref "JP10") (pin "3") (pinfunction "3_3") (pintype "passive"))
      (node (ref "JP4") (pin "2") (pinfunction "2_2") (pintype "passive"))
      (node (ref "SJ11") (pin "P$2") (pinfunction "2_P$2") (pintype "passive"))
      (node (ref "SJ14") (pin "P$2") (pinfunction "2_P$2") (pintype "passive"))
      (node (ref "SJ2") (pin "P$2") (pinfunction "2_P$2") (pintype "passive"))
      (node (ref "SJ5") (pin "P$2") (pinfunction "2_P$2") (pintype "passive"))
      (node (ref "SJ8") (pin "P$2") (pinfunction "2_P$2") (pintype "passive"))
      (node (ref "U$2") (pin "6") (pinfunction "VDD_6") (pintype "power_in"))
      (node (ref "U$3") (pin "6") (pinfunction "VDD_6") (pintype "power_in"))
      (node (ref "U$4") (pin "6") (pinfunction "VDD_6") (pintype "power_in"))
      (node (ref "U$5") (pin "6") (pinfunction "VDD_6") (pintype "power_in"))
    )
    (net (code "4") (name "/AGND") (class "Default")
      (node (ref "U$1") (pin "AGND") (pinfunction "AGND_AGND") (pintype "power_in"))
    )
    (net (code "5") (name "/AVDD") (class "Default")
      (node (ref "U$1") (pin "AVDD") (pinfunction "AVDD_AVDD") (pintype "power_in"))
    )
    (net (code "6") (name "/CANH") (class "Default")
      (node (ref "IC7") (pin "7") (pinfunction "CANH_7") (pintype "bidirectional"))
      (node (ref "J1") (pin "1") (pinfunction "1_1") (pintype "passive"))
      (node (ref "J2") (pin "1") (pinfunction "1_1") (pintype "passive"))
      (node (ref "U$6") (pin "7") (pinfunction "CANH_7") (pintype "bidirectional"))
    )
    (net (code "7") (name "/CANL") (class "Default")
      (node (ref "IC7") (pin "6") (pinfunction "CANL_6") (pintype "bidirectional"))
      (node (ref "J1") (pin "2") (pinfunction "2_2") (pintype "passive"))
      (node (ref "J2") (pin "2") (pinfunction "2_2") (pintype "passive"))
      (node (ref "U$6") (pin "6") (pinfunction "CANL_6") (pintype "bidirectional"))
    )
    (net (code "8") (name "/TIN1") (class "Default")
      (node (ref "IC9") (pin "3") (pinfunction "+IN_3") (pintype "input"))
      (node (ref "U$1") (pin "PB2") (pinfunction "PB2_PB2") (pintype "bidirectional"))
      (node (ref "U$3") (pin "4") (pinfunction "I_4") (pintype "input"))
    )
    (net (code "9") (name "/TIN2") (class "Default")
      (node (ref "IC9") (pin "5") (pinfunction "+IN_5") (pintype "input"))
      (node (ref "U$1") (pin "PB1") (pinfunction "PB1_PB1") (pintype "bidirectional"))
      (node (ref "U$2") (pin "2") (pinfunction "I_2") (pintype "input"))
    )
    (net (code "10") (name "/TIN5") (class "Default")
      (node (ref "IC6") (pin "3") (pinfunction "+IN_3") (pintype "input"))
      (node (ref "U$1") (pin "PA4") (pinfunction "PA4_PA4") (pintype "bidirectional"))
      (node (ref "U$5") (pin "4") (pinfunction "I_4") (pintype "input"))
    )
    (net (code "11") (name "/TIN6") (class "Default")
      (node (ref "IC6") (pin "5") (pinfunction "+IN_5") (pintype "input"))
      (node (ref "U$1") (pin "PC0") (pinfunction "PC0_PC0") (pintype "bidirectional"))
      (node (ref "U$4") (pin "2") (pinfunction "I_2") (pintype "input"))
    )
    (net (code "12") (name "/TIN7") (class "Default")
      (node (ref "IC6") (pin "10") (pinfunction "+IN_10") (pintype "input"))
      (node (ref "U$1") (pin "PC3") (pinfunction "PC3_PC3") (pintype "bidirectional"))
      (node (ref "U$4") (pin "4") (pinfunction "I_4") (pintype "input"))
    )
    (net (code "13") (name "/TIN8") (class "Default")
      (node (ref "IC6") (pin "12") (pinfunction "+IN_12") (pintype "input"))
      (node (ref "U$1") (pin "PA0") (pinfunction "PA0_PA0") (pintype "bidirectional"))
      (node (ref "U$5") (pin "2") (pinfunction "I_2") (pintype "input"))
    )
    (net (code "14") (name "/U5V") (class "Default")
      (node (ref "U$1") (pin "U5V") (pinfunction "U5V_U5V") (pintype "power_in"))
    )
    (net (code "15") (name "/VBAT") (class "Default")
      (node (ref "U$1") (pin "VBAT") (pinfunction "VBAT_VBAT") (pintype "power_in"))
    )
    (net (code "16") (name "/VDD") (class "Default")
      (node (ref "U$1") (pin "VDD") (pinfunction "VDD_VDD") (pintype "power_in"))
    )
    (net (code "17") (name "CANRX") (class "Default")
      (node (ref "IC7") (pin "4") (pinfunction "RXD_4") (pintype "output"))
      (node (ref "U$1") (pin "PB8") (pinfunction "PB8_PB8") (pintype "bidirectional"))
      (node (ref "U$6") (pin "4") (pinfunction "RXD_4") (pintype "bidirectional"))
    )
    (net (code "18") (name "CANTX") (class "Default")
      (node (ref "IC7") (pin "1") (pinfunction "TXD_1") (pintype "input"))
      (node (ref "U$1") (pin "PB9") (pinfunction "PB9_PB9") (pintype "bidirectional"))
      (node (ref "U$6") (pin "1") (pinfunction "TXD_1") (pintype "bidirectional"))
    )
    (net (code "19") (name "E_CS") (class "Default")
      (node (ref "JP9") (pin "4") (pinfunction "4_4") (pintype "passive"))
      (node (ref "R23") (pin "2") (pinfunction "2_2") (pintype "passive"))
      (node (ref "U$1") (pin "PC10") (pinfunction "PC10_PC10") (pintype "bidirectional"))
    )
    (net (code "20") (name "E_LAT") (class "Default")
      (node (ref "JP10") (pin "1") (pinfunction "1_1") (pintype "passive"))
      (node (ref "R22") (pin "2") (pinfunction "2_2") (pintype "passive"))
      (node (ref "U$1") (pin "PC11") (pinfunction "PC11_PC11") (pintype "bidirectional"))
    )
    (net (code "21") (name "GND") (class "Default")
      (node (ref "AP1509") (pin "4") (pinfunction "SD_4") (pintype "bidirectional"))
      (node (ref "AP1509") (pin "5") (pinfunction "GND1_5") (pintype "power_in"))
      (node (ref "AP1509") (pin "6") (pinfunction "GND2_6") (pintype "power_in"))
      (node (ref "AP1509") (pin "7") (pinfunction "GND3_7") (pintype "power_in"))
      (node (ref "AP1509") (pin "8") (pinfunction "GND4_8") (pintype "power_in"))
      (node (ref "C1") (pin "2") (pinfunction "2_2") (pintype "passive"))
      (node (ref "C10") (pin "2") (pinfunction "2_2") (pintype "passive"))
      (node (ref "C11") (pin "2") (pinfunction "2_2") (pintype "passive"))
      (node (ref "C2") (pin "-") (pinfunction "-_-") (pintype "passive"))
      (node (ref "C3") (pin "2") (pinfunction "2_2") (pintype "passive"))
      (node (ref "C4") (pin "2") (pinfunction "2_2") (pintype "passive"))
      (node (ref "C5") (pin "2") (pinfunction "2_2") (pintype "passive"))
      (node (ref "C6") (pin "2") (pinfunction "2_2") (pintype "passive"))
      (node (ref "C7") (pin "2") (pinfunction "2_2") (pintype "passive"))
      (node (ref "C8") (pin "2") (pinfunction "2_2") (pintype "passive"))
      (node (ref "C9") (pin "2") (pinfunction "2_2") (pintype "passive"))
      (node (ref "D1") (pin "A") (pinfunction "A_A") (pintype "passive"))
      (node (ref "IC1") (pin "6") (pinfunction "INH_6") (pintype "input"))
      (node (ref "IC1") (pin "8") (pinfunction "GND_8") (pintype "power_in"))
      (node (ref "IC10") (pin "2") (pinfunction "GNDSIG_2") (pintype "input"))
      (node (ref "IC10") (pin "3") (pinfunction "~{ON/OFF}_3") (pintype "input"))
      (node (ref "IC10") (pin "4") (pinfunction "GND_4") (pintype "power_in"))
      (node (ref "IC3") (pin "13") (pinfunction "G_13") (pintype "input"))
      (node (ref "IC3") (pin "8") (pinfunction "GND_8") (pintype "power_in"))
      (node (ref "IC4") (pin "6") (pinfunction "INH_6") (pintype "input"))
      (node (ref "IC4") (pin "8") (pinfunction "GND_8") (pintype "power_in"))
      (node (ref "IC5") (pin "13") (pinfunction "G_13") (pintype "input"))
      (node (ref "IC5") (pin "8") (pinfunction "GND_8") (pintype "power_in"))
      (node (ref "IC6") (pin "11") (pinfunction "V-_11") (pintype "power_in"))
      (node (ref "IC7") (pin "2") (pinfunction "GND_2") (pintype "power_in"))
      (node (ref "IC9") (pin "11") (pinfunction "V-_11") (pintype "power_in"))
      (node (ref "J1") (pin "3") (pinfunction "3_3") (pintype "passive"))
      (node (ref "J1") (pin "6") (pinfunction "6_6") (pintype "passive"))
      (node (ref "J1") (pin "7") (pinfunction "7_7") (pintype "passive"))
      (node (ref "J2") (pin "3") (pinfunction "3_3") (pintype "passive"))
      (node (ref "J2") (pin "6") (pinfunction "6_6") (pintype "passive"))
      (node (ref "J2") (pin "7") (pinfunction "7_7") (pintype "passive"))
      (node (ref "J3") (pin "1") (pinfunction "1_1") (pintype "passive"))
      (node (ref "JP10") (pin "4") (pinfunction "4_4") (pintype "passive"))
      (node (ref "JP11") (pin "5") (pinfunction "5_5") (pintype "passive"))
      (node (ref "JP11") (pin "6") (pinfunction "6_6") (pintype "passive"))
      (node (ref "JP12") (pin "5") (pinfunction "5_5") (pintype "passive"))
      (node (ref "JP12") (pin "6") (pinfunction "6_6") (pintype "passive"))
      (node (ref "JP13") (pin "5") (pinfunction "5_5") (pintype "passive"))
      (node (ref "JP14") (pin "5") (pinfunction "5_5") (pintype "passive"))
      (node (ref "JP15") (pin "5") (pinfunction "5_5") (pintype "passive"))
      (node (ref "JP16") (pin "5") (pinfunction "5_5") (pintype "passive"))
      (node (ref "JP16") (pin "6") (pinfunction "6_6") (pintype "passive"))
      (node (ref "JP7") (pin "5") (pinfunction "5_5") (pintype "passive"))
      (node (ref "JP7") (pin "6") (pinfunction "6_6") (pintype "passive"))
      (node (ref "JP8") (pin "4") (pinfunction "4_4") (pintype "passive"))
      (node (ref "Q1") (pin "2") (pinfunction "S_2") (pintype "passive"))
      (node (ref "Q10") (pin "2") (pinfunction "S_2") (pintype "passive"))
      (node (ref "Q11") (pin "2") (pinfunction "S_2") (pintype "passive"))
      (node (ref "Q12") (pin "2") (pinfunction "S_2") (pintype "passive"))
      (node (ref "Q13") (pin "2") (pinfunction "S_2") (pintype "passive"))
      (node (ref "Q14") (pin "2") (pinfunction "S_2") (pintype "passive"))
      (node (ref "Q15") (pin "2") (pinfunction "S_2") (pintype "passive"))
      (node (ref "Q16") (pin "2") (pinfunction "S_2") (pintype "passive"))
      (node (ref "Q2") (pin "2") (pinfunction "S_2") (pintype "passive"))
      (node (ref "Q3") (pin "2") (pinfunction "S_2") (pintype "passive"))
      (node (ref "Q4") (pin "2") (pinfunction "S_2") (pintype "passive"))
      (node (ref "Q5") (pin "2") (pinfunction "S_2") (pintype "passive"))
      (node (ref "Q6") (pin "2") (pinfunction "S_2") (pintype "passive"))
      (node (ref "Q7") (pin "2") (pinfunction "S_2") (pintype "passive"))
      (node (ref "Q8") (pin "2") (pinfunction "S_2") (pintype "passive"))
      (node (ref "Q9") (pin "2") (pinfunction "S_2") (pintype "passive"))
      (node (ref "R2") (pin "1") (pinfunction "1_1") (pintype "passive"))
      (node (ref "R61") (pin "2") (pinfunction "2_2") (pintype "passive"))
      (node (ref "SJ12") (pin "P$2") (pinfunction "2_P$2") (pintype "passive"))
      (node (ref "SJ3") (pin "2") (pinfunction "2_2") (pintype "passive"))
      (node (ref "SJ6") (pin "P$2") (pinfunction "2_P$2") (pintype "passive"))
      (node (ref "SJ9") (pin "2") (pinfunction "2_2") (pintype "passive"))
      (node (ref "U$1") (pin "GND3") (pinfunction "GND3_GND3") (pintype "power_in"))
      (node (ref "U$1") (pin "GND4") (pinfunction "GND4_GND4") (pintype "power_in"))
      (node (ref "U$1") (pin "GND5") (pinfunction "GND5_GND5") (pintype "power_in"))
      (node (ref "U$1") (pin "GND6") (pinfunction "GND6_GND6") (pintype "power_in"))
      (node (ref "U$1") (pin "GND7") (pinfunction "GND7_GND7") (pintype "power_in"))
      (node (ref "U$1") (pin "GND8") (pinfunction "GND8_GND8") (pintype "power_in"))
      (node (ref "U$2") (pin "3") (pinfunction "VSS_3") (pintype "power_in"))
      (node (ref "U$3") (pin "3") (pinfunction "VSS_3") (pintype "power_in"))
      (node (ref "U$4") (pin "3") (pinfunction "VSS_3") (pintype "power_in"))
      (node (ref "U$5") (pin "3") (pinfunction "VSS_3") (pintype "power_in"))
      (node (ref "U$6") (pin "2") (pinfunction "VSS_2") (pintype "power_in"))
      (node (ref "X1") (pin "2") (pinfunction "2_2") (pintype "passive"))
    )
    (net (code "22") (name "I2CSCL") (class "Default")
      (node (ref "JP8") (pin "2") (pinfunction "2_2") (pintype "passive"))
      (node (ref "R63") (pin "2") (pinfunction "2_2") (pintype "passive"))
      (node (ref "U$1") (pin "PB6") (pinfunction "PB6_PB6") (pintype "bidirectional"))
    )
    (net (code "23") (name "I2CSDA") (class "Default")
      (node (ref "JP8") (pin "1") (pinfunction "1_1") (pintype "passive"))
      (node (ref "R62") (pin "2") (pinfunction "2_2") (pintype "passive"))
      (node (ref "U$1") (pin "PB7") (pinfunction "PB7_PB7") (pintype "bidirectional"))
    )
    (net (code "24") (name "ILAT") (class "Default")
      (node (ref "IC1") (pin "15") (pinfunction "SH/~{LD}_15") (pintype "input"))
      (node (ref "IC4") (pin "15") (pinfunction "SH/~{LD}_15") (pintype "input"))
      (node (ref "U$1") (pin "PA6") (pinfunction "PA6_PA6") (pintype "bidirectional"))
    )
    (net (code "25") (name "MISO") (class "Default")
      (node (ref "JP9") (pin "1") (pinfunction "1_1") (pintype "passive"))
      (node (ref "U$1") (pin "PB4") (pinfunction "PB4_PB4") (pintype "bidirectional"))
    )
    (net (code "26") (name "MISO2") (class "Default")
      (node (ref "IC4") (pin "13") (pinfunction "QH_13") (pintype "output"))
      (node (ref "SJ13") (pin "P$2") (pinfunction "2_P$2") (pintype "passive"))
      (node (ref "U$1") (pin "PC2") (pinfunction "PC2_PC2") (pintype "bidirectional"))
    )
    (net (code "27") (name "MOSI") (class "Default")
      (node (ref "IC5") (pin "14") (pinfunction "SER_14") (pintype "input"))
      (node (ref "R20") (pin "1") (pinfunction "1_1") (pintype "passive"))
      (node (ref "SJ15") (pin "1") (pinfunction "1_1") (pintype "passive"))
      (node (ref "SJ17") (pin "P$2") (pinfunction "2_P$2") (pintype "passive"))
      (node (ref "U$1") (pin "PB5") (pinfunction "PB5_PB5") (pintype "bidirectional"))
    )
    (net (code "28") (name "Net-(AP1509-VOUT)") (class "Default")
      (node (ref "AP1509") (pin "2") (pinfunction "VOUT_2") (pintype "bidirectional"))
      (node (ref "D1") (pin "C") (pinfunction "C_C") (pintype "passive"))
      (node (ref "IC10") (pin "7") (pinfunction "OUT_7") (pintype "passive"))
      (node (ref "L1") (pin "2") (pinfunction "2_2") (pintype "passive"))
    )
    (net (code "29") (name "Net-(D2-PadA)") (class "Default")
      (node (ref "D2") (pin "A") (pinfunction "A_A") (pintype "passive"))
      (node (ref "JP4") (pin "4") (pinfunction "4_4") (pintype "passive"))
    )
    (net (code "30") (name "Net-(D2-PadC)") (class "Default")
      (node (ref "D2") (pin "C") (pinfunction "C_C") (pintype "passive"))
      (node (ref "JP4") (pin "1") (pinfunction "1_1") (pintype "passive"))
    )
    (net (code "31") (name "Net-(IC1A-A)") (class "Default")
      (node (ref "IC1") (pin "2") (pinfunction "A_2") (pintype "input"))
      (node (ref "R36") (pin "1") (pinfunction "1_1") (pintype "passive"))
      (node (ref "RN4") (pin "9") (pinfunction "2_9") (pintype "passive"))
    )
    (net (code "32") (name "Net-(IC1A-B)") (class "Default")
      (node (ref "IC1") (pin "3") (pinfunction "B_3") (pintype "input"))
      (node (ref "R37") (pin "1") (pinfunction "1_1") (pintype "passive"))
      (node (ref "RN4") (pin "10") (pinfunction "2_10") (pintype "passive"))
    )
    (net (code "33") (name "Net-(IC1A-C)") (class "Default")
      (node (ref "IC1") (pin "4") (pinfunction "C_4") (pintype "input"))
      (node (ref "R38") (pin "1") (pinfunction "1_1") (pintype "passive"))
      (node (ref "RN4") (pin "11") (pinfunction "2_11") (pintype "passive"))
    )
    (net (code "34") (name "Net-(IC1A-D)") (class "Default")
      (node (ref "IC1") (pin "5") (pinfunction "D_5") (pintype "input"))
      (node (ref "R39") (pin "1") (pinfunction "1_1") (pintype "passive"))
      (node (ref "RN4") (pin "12") (pinfunction "2_12") (pintype "passive"))
    )
    (net (code "35") (name "Net-(IC1A-E)") (class "Default")
      (node (ref "IC1") (pin "10") (pinfunction "E_10") (pintype "input"))
      (node (ref "R41") (pin "1") (pinfunction "1_1") (pintype "passive"))
      (node (ref "RN4") (pin "13") (pinfunction "2_13") (pintype "passive"))
    )
    (net (code "36") (name "Net-(IC1A-F)") (class "Default")
      (node (ref "IC1") (pin "11") (pinfunction "F_11") (pintype "input"))
      (node (ref "R42") (pin "1") (pinfunction "1_1") (pintype "passive"))
      (node (ref "RN4") (pin "14") (pinfunction "2_14") (pintype "passive"))
    )
    (net (code "37") (name "Net-(IC1A-G)") (class "Default")
      (node (ref "IC1") (pin "12") (pinfunction "G_12") (pintype "input"))
      (node (ref "R43") (pin "1") (pinfunction "1_1") (pintype "passive"))
      (node (ref "RN4") (pin "15") (pinfunction "2_15") (pintype "passive"))
    )
    (net (code "38") (name "Net-(IC1A-H)") (class "Default")
      (node (ref "IC1") (pin "14") (pinfunction "H_14") (pintype "input"))
      (node (ref "R44") (pin "1") (pinfunction "1_1") (pintype "passive"))
      (node (ref "RN4") (pin "16") (pinfunction "2_16") (pintype "passive"))
    )
    (net (code "39") (name "Net-(IC2-CD+)") (class "Default")
      (node (ref "IC2") (pin "10") (pinfunction "CD+_10") (pintype "passive"))
      (node (ref "SJ4") (pin "P$1") (pinfunction "1_P$1") (pintype "passive"))
      (node (ref "SJ5") (pin "P$1") (pinfunction "1_P$1") (pintype "passive"))
      (node (ref "SJ6") (pin "P$1") (pinfunction "1_P$1") (pintype "passive"))
    )
    (net (code "40") (name "Net-(IC2-GND)") (class "Default")
      (node (ref "IC2") (pin "9") (pinfunction "GND_9") (pintype "power_in"))
      (node (ref "SJ1") (pin "P$1") (pinfunction "1_P$1") (pintype "passive"))
      (node (ref "SJ2") (pin "P$1") (pinfunction "1_P$1") (pintype "passive"))
      (node (ref "SJ3") (pin "1") (pinfunction "1_1") (pintype "passive"))
    )
    (net (code "41") (name "Net-(IC2-I1)") (class "Default")
      (node (ref "IC2") (pin "1") (pinfunction "I1_1") (pintype "input"))
      (node (ref "IC5") (pin "15") (pinfunction "QA_15") (pintype "tri_state"))
      (node (ref "R3") (pin "1") (pinfunction "1_1") (pintype "passive"))
    )
    (net (code "42") (name "Net-(IC2-I2)") (class "Default")
      (node (ref "IC2") (pin "2") (pinfunction "I2_2") (pintype "input"))
      (node (ref "IC5") (pin "1") (pinfunction "QB_1") (pintype "tri_state"))
      (node (ref "R4") (pin "1") (pinfunction "1_1") (pintype "passive"))
    )
    (net (code "43") (name "Net-(IC2-I3)") (class "Default")
      (node (ref "IC2") (pin "3") (pinfunction "I3_3") (pintype "input"))
      (node (ref "IC5") (pin "2") (pinfunction "QC_2") (pintype "tri_state"))
      (node (ref "R5") (pin "1") (pinfunction "1_1") (pintype "passive"))
    )
    (net (code "44") (name "Net-(IC2-I4)") (class "Default")
      (node (ref "IC2") (pin "4") (pinfunction "I4_4") (pintype "input"))
      (node (ref "IC5") (pin "3") (pinfunction "QD_3") (pintype "tri_state"))
      (node (ref "R6") (pin "1") (pinfunction "1_1") (pintype "passive"))
    )
    (net (code "45") (name "Net-(IC2-I5)") (class "Default")
      (node (ref "IC2") (pin "5") (pinfunction "I5_5") (pintype "input"))
      (node (ref "IC5") (pin "4") (pinfunction "QE_4") (pintype "tri_state"))
      (node (ref "R7") (pin "1") (pinfunction "1_1") (pintype "passive"))
    )
    (net (code "46") (name "Net-(IC2-I6)") (class "Default")
      (node (ref "IC2") (pin "6") (pinfunction "I6_6") (pintype "input"))
      (node (ref "IC5") (pin "5") (pinfunction "QF_5") (pintype "tri_state"))
      (node (ref "R8") (pin "1") (pinfunction "1_1") (pintype "passive"))
    )
    (net (code "47") (name "Net-(IC2-I7)") (class "Default")
      (node (ref "IC2") (pin "7") (pinfunction "I7_7") (pintype "input"))
      (node (ref "IC5") (pin "6") (pinfunction "QG_6") (pintype "tri_state"))
      (node (ref "R9") (pin "1") (pinfunction "1_1") (pintype "passive"))
    )
    (net (code "48") (name "Net-(IC2-I8)") (class "Default")
      (node (ref "IC2") (pin "8") (pinfunction "I8_8") (pintype "input"))
      (node (ref "IC5") (pin "7") (pinfunction "QH_7") (pintype "tri_state"))
      (node (ref "R10") (pin "1") (pinfunction "1_1") (pintype "passive"))
    )
    (net (code "49") (name "Net-(IC2-O1)") (class "Default")
      (node (ref "IC2") (pin "18") (pinfunction "O1_18") (pintype "open_collector"))
      (node (ref "JP1") (pin "1") (pinfunction "1_1") (pintype "passive"))
      (node (ref "Q1") (pin "3") (pinfunction "D_3") (pintype "passive"))
    )
    (net (code "50") (name "Net-(IC2-O2)") (class "Default")
      (node (ref "IC2") (pin "17") (pinfunction "O2_17") (pintype "open_collector"))
      (node (ref "JP1") (pin "2") (pinfunction "2_2") (pintype "passive"))
      (node (ref "Q2") (pin "3") (pinfunction "D_3") (pintype "passive"))
    )
    (net (code "51") (name "Net-(IC2-O3)") (class "Default")
      (node (ref "IC2") (pin "16") (pinfunction "O3_16") (pintype "open_collector"))
      (node (ref "JP1") (pin "3") (pinfunction "3_3") (pintype "passive"))
      (node (ref "Q3") (pin "3") (pinfunction "D_3") (pintype "passive"))
    )
    (net (code "52") (name "Net-(IC2-O4)") (class "Default")
      (node (ref "IC2") (pin "15") (pinfunction "O4_15") (pintype "open_collector"))
      (node (ref "JP1") (pin "4") (pinfunction "4_4") (pintype "passive"))
      (node (ref "Q4") (pin "3") (pinfunction "D_3") (pintype "passive"))
    )
    (net (code "53") (name "Net-(IC2-O5)") (class "Default")
      (node (ref "IC2") (pin "14") (pinfunction "O5_14") (pintype "open_collector"))
      (node (ref "JP1") (pin "5") (pinfunction "5_5") (pintype "passive"))
      (node (ref "Q5") (pin "3") (pinfunction "D_3") (pintype "passive"))
    )
    (net (code "54") (name "Net-(IC2-O6)") (class "Default")
      (node (ref "IC2") (pin "13") (pinfunction "O6_13") (pintype "open_collector"))
      (node (ref "JP1") (pin "6") (pinfunction "6_6") (pintype "passive"))
      (node (ref "Q6") (pin "3") (pinfunction "D_3") (pintype "passive"))
    )
    (net (code "55") (name "Net-(IC2-O7)") (class "Default")
      (node (ref "IC2") (pin "12") (pinfunction "O7_12") (pintype "open_collector"))
      (node (ref "JP1") (pin "7") (pinfunction "7_7") (pintype "passive"))
      (node (ref "Q7") (pin "3") (pinfunction "D_3") (pintype "passive"))
    )
    (net (code "56") (name "Net-(IC2-O8)") (class "Default")
      (node (ref "IC2") (pin "11") (pinfunction "O8_11") (pintype "open_collector"))
      (node (ref "JP1") (pin "8") (pinfunction "8_8") (pintype "passive"))
      (node (ref "Q8") (pin "3") (pinfunction "D_3") (pintype "passive"))
    )
    (net (code "57") (name "Net-(IC3A-QA)") (class "Default")
      (node (ref "IC3") (pin "15") (pinfunction "QA_15") (pintype "tri_state"))
      (node (ref "IC8") (pin "1") (pinfunction "I1_1") (pintype "input"))
      (node (ref "R11") (pin "1") (pinfunction "1_1") (pintype "passive"))
    )
    (net (code "58") (name "Net-(IC3A-QB)") (class "Default")
      (node (ref "IC3") (pin "1") (pinfunction "QB_1") (pintype "tri_state"))
      (node (ref "IC8") (pin "2") (pinfunction "I2_2") (pintype "input"))
      (node (ref "R12") (pin "1") (pinfunction "1_1") (pintype "passive"))
    )
    (net (code "59") (name "Net-(IC3A-QC)") (class "Default")
      (node (ref "IC3") (pin "2") (pinfunction "QC_2") (pintype "tri_state"))
      (node (ref "IC8") (pin "3") (pinfunction "I3_3") (pintype "input"))
      (node (ref "R13") (pin "1") (pinfunction "1_1") (pintype "passive"))
    )
    (net (code "60") (name "Net-(IC3A-QD)") (class "Default")
      (node (ref "IC3") (pin "3") (pinfunction "QD_3") (pintype "tri_state"))
      (node (ref "IC8") (pin "4") (pinfunction "I4_4") (pintype "input"))
      (node (ref "R14") (pin "1") (pinfunction "1_1") (pintype "passive"))
    )
    (net (code "61") (name "Net-(IC3A-QE)") (class "Default")
      (node (ref "IC3") (pin "4") (pinfunction "QE_4") (pintype "tri_state"))
      (node (ref "IC8") (pin "5") (pinfunction "I5_5") (pintype "input"))
      (node (ref "R15") (pin "1") (pinfunction "1_1") (pintype "passive"))
    )
    (net (code "62") (name "Net-(IC3A-QF)") (class "Default")
      (node (ref "IC3") (pin "5") (pinfunction "QF_5") (pintype "tri_state"))
      (node (ref "IC8") (pin "6") (pinfunction "I6_6") (pintype "input"))
      (node (ref "R16") (pin "1") (pinfunction "1_1") (pintype "passive"))
    )
    (net (code "63") (name "Net-(IC3A-QG)") (class "Default")
      (node (ref "IC3") (pin "6") (pinfunction "QG_6") (pintype "tri_state"))
      (node (ref "IC8") (pin "7") (pinfunction "I7_7") (pintype "input"))
      (node (ref "R17") (pin "1") (pinfunction "1_1") (pintype "passive"))
    )
    (net (code "64") (name "Net-(IC3A-QH)") (class "Default")
      (node (ref "IC3") (pin "7") (pinfunction "QH_7") (pintype "tri_state"))
      (node (ref "IC8") (pin "8") (pinfunction "I8_8") (pintype "input"))
      (node (ref "R18") (pin "1") (pinfunction "1_1") (pintype "passive"))
    )
    (net (code "65") (name "Net-(IC4A-A)") (class "Default")
      (node (ref "IC4") (pin "2") (pinfunction "A_2") (pintype "input"))
      (node (ref "R28") (pin "1") (pinfunction "1_1") (pintype "passive"))
      (node (ref "RN1") (pin "9") (pinfunction "2_9") (pintype "passive"))
    )
    (net (code "66") (name "Net-(IC4A-B)") (class "Default")
      (node (ref "IC4") (pin "3") (pinfunction "B_3") (pintype "input"))
      (node (ref "R29") (pin "1") (pinfunction "1_1") (pintype "passive"))
      (node (ref "RN1") (pin "10") (pinfunction "2_10") (pintype "passive"))
    )
    (net (code "67") (name "Net-(IC4A-C)") (class "Default")
      (node (ref "IC4") (pin "4") (pinfunction "C_4") (pintype "input"))
      (node (ref "R30") (pin "1") (pinfunction "1_1") (pintype "passive"))
      (node (ref "RN1") (pin "11") (pinfunction "2_11") (pintype "passive"))
    )
    (net (code "68") (name "Net-(IC4A-D)") (class "Default")
      (node (ref "IC4") (pin "5") (pinfunction "D_5") (pintype "input"))
      (node (ref "R31") (pin "1") (pinfunction "1_1") (pintype "passive"))
      (node (ref "RN1") (pin "12") (pinfunction "2_12") (pintype "passive"))
    )
    (net (code "69") (name "Net-(IC4A-E)") (class "Default")
      (node (ref "IC4") (pin "10") (pinfunction "E_10") (pintype "input"))
      (node (ref "R32") (pin "1") (pinfunction "1_1") (pintype "passive"))
      (node (ref "RN1") (pin "13") (pinfunction "2_13") (pintype "passive"))
    )
    (net (code "70") (name "Net-(IC4A-F)") (class "Default")
      (node (ref "IC4") (pin "11") (pinfunction "F_11") (pintype "input"))
      (node (ref "R33") (pin "1") (pinfunction "1_1") (pintype "passive"))
      (node (ref "RN1") (pin "14") (pinfunction "2_14") (pintype "passive"))
    )
    (net (code "71") (name "Net-(IC4A-G)") (class "Default")
      (node (ref "IC4") (pin "12") (pinfunction "G_12") (pintype "input"))
      (node (ref "R34") (pin "1") (pinfunction "1_1") (pintype "passive"))
      (node (ref "RN1") (pin "15") (pinfunction "2_15") (pintype "passive"))
    )
    (net (code "72") (name "Net-(IC4A-H)") (class "Default")
      (node (ref "IC4") (pin "14") (pinfunction "H_14") (pintype "input"))
      (node (ref "R35") (pin "1") (pinfunction "1_1") (pintype "passive"))
      (node (ref "RN1") (pin "16") (pinfunction "2_16") (pintype "passive"))
    )
    (net (code "73") (name "Net-(IC6A--IN)") (class "Default")
      (node (ref "IC6") (pin "13") (pinfunction "-IN_13") (pintype "input"))
      (node (ref "IC6") (pin "2") (pinfunction "-IN_2") (pintype "input"))
      (node (ref "IC6") (pin "6") (pinfunction "-IN_6") (pintype "input"))
      (node (ref "IC6") (pin "9") (pinfunction "-IN_9") (pintype "input"))
      (node (ref "IC9") (pin "13") (pinfunction "-IN_13") (pintype "input"))
      (node (ref "IC9") (pin "2") (pinfunction "-IN_2") (pintype "input"))
      (node (ref "IC9") (pin "6") (pinfunction "-IN_6") (pintype "input"))
      (node (ref "IC9") (pin "9") (pinfunction "-IN_9") (pintype "input"))
      (node (ref "R1") (pin "1") (pinfunction "1_1") (pintype "passive"))
      (node (ref "R2") (pin "2") (pinfunction "2_2") (pintype "passive"))
    )
    (net (code "74") (name "Net-(IC6A-OUT)") (class "Default")
      (node (ref "IC6") (pin "1") (pinfunction "OUT_1") (pintype "output"))
      (node (ref "JP15") (pin "3") (pinfunction "3_3") (pintype "passive"))
      (node (ref "JP5") (pin "3") (pinfunction "3_3") (pintype "passive"))
      (node (ref "U$5") (pin "5") (pinfunction "O_5") (pintype "output"))
    )
    (net (code "75") (name "Net-(IC6B-OUT)") (class "Default")
      (node (ref "IC6") (pin "7") (pinfunction "OUT_7") (pintype "output"))
      (node (ref "JP15") (pin "1") (pinfunction "1_1") (pintype "passive"))
      (node (ref "JP5") (pin "1") (pinfunction "1_1") (pintype "passive"))
      (node (ref "U$4") (pin "7") (pinfunction "O_7") (pintype "output"))
    )
    (net (code "76") (name "Net-(IC6C-OUT)") (class "Default")
      (node (ref "IC6") (pin "8") (pinfunction "OUT_8") (pintype "output"))
      (node (ref "JP15") (pin "2") (pinfunction "2_2") (pintype "passive"))
      (node (ref "JP5") (pin "2") (pinfunction "2_2") (pintype "passive"))
      (node (ref "U$4") (pin "5") (pinfunction "O_5") (pintype "output"))
    )
    (net (code "77") (name "Net-(IC6D-OUT)") (class "Default")
      (node (ref "IC6") (pin "14") (pinfunction "OUT_14") (pintype "output"))
      (node (ref "JP15") (pin "4") (pinfunction "4_4") (pintype "passive"))
      (node (ref "JP5") (pin "4") (pinfunction "4_4") (pintype "passive"))
      (node (ref "U$5") (pin "7") (pinfunction "O_7") (pintype "output"))
    )
    (net (code "78") (name "Net-(IC7-RS)") (class "Default")
      (node (ref "IC7") (pin "8") (pinfunction "RS_8") (pintype "input"))
      (node (ref "R61") (pin "1") (pinfunction "1_1") (pintype "passive"))
      (node (ref "U$6") (pin "8") (pinfunction "RS_8") (pintype "bidirectional"))
    )
    (net (code "79") (name "Net-(IC7-VREF)") (class "Default")
      (node (ref "IC7") (pin "5") (pinfunction "VREF_5") (pintype "output"))
      (node (ref "SJ18") (pin "P$2") (pinfunction "2_P$2") (pintype "passive"))
      (node (ref "U$6") (pin "5") (pinfunction "VREF_5") (pintype "bidirectional"))
    )
    (net (code "80") (name "Net-(IC8-CD+)") (class "Default")
      (node (ref "IC8") (pin "10") (pinfunction "CD+_10") (pintype "passive"))
      (node (ref "SJ10") (pin "P$1") (pinfunction "1_P$1") (pintype "passive"))
      (node (ref "SJ11") (pin "P$1") (pinfunction "1_P$1") (pintype "passive"))
      (node (ref "SJ12") (pin "P$1") (pinfunction "1_P$1") (pintype "passive"))
    )
    (net (code "81") (name "Net-(IC8-GND)") (class "Default")
      (node (ref "IC8") (pin "9") (pinfunction "GND_9") (pintype "power_in"))
      (node (ref "SJ7") (pin "P$1") (pinfunction "1_P$1") (pintype "passive"))
      (node (ref "SJ8") (pin "P$1") (pinfunction "1_P$1") (pintype "passive"))
      (node (ref "SJ9") (pin "1") (pinfunction "1_1") (pintype "passive"))
    )
    (net (code "82") (name "Net-(IC8-O1)") (class "Default")
      (node (ref "IC8") (pin "18") (pinfunction "O1_18") (pintype "open_collector"))
      (node (ref "JP6") (pin "1") (pinfunction "1_1") (pintype "passive"))
      (node (ref "Q9") (pin "3") (pinfunction "D_3") (pintype "passive"))
    )
    (net (code "83") (name "Net-(IC8-O2)") (class "Default")
      (node (ref "IC8") (pin "17") (pinfunction "O2_17") (pintype "open_collector"))
      (node (ref "JP6") (pin "2") (pinfunction "2_2") (pintype "passive"))
      (node (ref "Q10") (pin "3") (pinfunction "D_3") (pintype "passive"))
    )
    (net (code "84") (name "Net-(IC8-O3)") (class "Default")
      (node (ref "IC8") (pin "16") (pinfunction "O3_16") (pintype "open_collector"))
      (node (ref "JP6") (pin "3") (pinfunction "3_3") (pintype "passive"))
      (node (ref "Q11") (pin "3") (pinfunction "D_3") (pintype "passive"))
    )
    (net (code "85") (name "Net-(IC8-O4)") (class "Default")
      (node (ref "IC8") (pin "15") (pinfunction "O4_15") (pintype "open_collector"))
      (node (ref "JP6") (pin "4") (pinfunction "4_4") (pintype "passive"))
      (node (ref "Q12") (pin "3") (pinfunction "D_3") (pintype "passive"))
    )
    (net (code "86") (name "Net-(IC8-O5)") (class "Default")
      (node (ref "IC8") (pin "14") (pinfunction "O5_14") (pintype "open_collector"))
      (node (ref "JP6") (pin "5") (pinfunction "5_5") (pintype "passive"))
      (node (ref "Q13") (pin "3") (pinfunction "D_3") (pintype "passive"))
    )
    (net (code "87") (name "Net-(IC8-O6)") (class "Default")
      (node (ref "IC8") (pin "13") (pinfunction "O6_13") (pintype "open_collector"))
      (node (ref "JP6") (pin "6") (pinfunction "6_6") (pintype "passive"))
      (node (ref "Q14") (pin "3") (pinfunction "D_3") (pintype "passive"))
    )
    (net (code "88") (name "Net-(IC8-O7)") (class "Default")
      (node (ref "IC8") (pin "12") (pinfunction "O7_12") (pintype "open_collector"))
      (node (ref "JP6") (pin "7") (pinfunction "7_7") (pintype "passive"))
      (node (ref "Q15") (pin "3") (pinfunction "D_3") (pintype "passive"))
    )
    (net (code "89") (name "Net-(IC8-O8)") (class "Default")
      (node (ref "IC8") (pin "11") (pinfunction "O8_11") (pintype "open_collector"))
      (node (ref "JP6") (pin "8") (pinfunction "8_8") (pintype "passive"))
      (node (ref "Q16") (pin "3") (pinfunction "D_3") (pintype "passive"))
    )
    (net (code "90") (name "Net-(IC9A-OUT)") (class "Default")
      (node (ref "IC9") (pin "1") (pinfunction "OUT_1") (pintype "output"))
      (node (ref "JP15") (pin "9") (pinfunction "9_9") (pintype "passive"))
      (node (ref "JP5") (pin "7") (pinfunction "7_7") (pintype "passive"))
      (node (ref "U$3") (pin "5") (pinfunction "O_5") (pintype "output"))
    )
    (net (code "91") (name "Net-(IC9B-OUT)") (class "Default")
      (node (ref "IC9") (pin "7") (pinfunction "OUT_7") (pintype "output"))
      (node (ref "JP15") (pin "7") (pinfunction "7_7") (pintype "passive"))
      (node (ref "JP5") (pin "5") (pinfunction "5_5") (pintype "passive"))
      (node (ref "U$2") (pin "7") (pinfunction "O_7") (pintype "output"))
    )
    (net (code "92") (name "Net-(IC9C-OUT)") (class "Default")
      (node (ref "IC9") (pin "8") (pinfunction "OUT_8") (pintype "output"))
      (node (ref "JP15") (pin "8") (pinfunction "8_8") (pintype "passive"))
      (node (ref "JP5") (pin "6") (pinfunction "6_6") (pintype "passive"))
      (node (ref "U$2") (pin "5") (pinfunction "O_5") (pintype "output"))
    )
    (net (code "93") (name "Net-(IC9D-OUT)") (class "Default")
      (node (ref "IC9") (pin "14") (pinfunction "OUT_14") (pintype "output"))
      (node (ref "JP15") (pin "10") (pinfunction "10_10") (pintype "passive"))
      (node (ref "JP5") (pin "8") (pinfunction "8_8") (pintype "passive"))
      (node (ref "U$3") (pin "7") (pinfunction "O_7") (pintype "output"))
    )
    (net (code "94") (name "Net-(J1-Pad4)") (class "Default")
      (node (ref "J1") (pin "4") (pinfunction "4_4") (pintype "passive"))
      (node (ref "J2") (pin "4") (pinfunction "4_4") (pintype "passive"))
    )
    (net (code "95") (name "Net-(J1-Pad5)") (class "Default")
      (node (ref "J1") (pin "5") (pinfunction "5_5") (pintype "passive"))
      (node (ref "J2") (pin "5") (pinfunction "5_5") (pintype "passive"))
    )
    (net (code "96") (name "Net-(J1-Pad8)") (class "Default")
      (node (ref "J1") (pin "8") (pinfunction "8_8") (pintype "passive"))
      (node (ref "J2") (pin "8") (pinfunction "8_8") (pintype "passive"))
      (node (ref "R40") (pin "1") (pinfunction "1_1") (pintype "passive"))
    )
    (net (code "97") (name "Net-(JP4-Pad3)") (class "Default")
      (node (ref "JP4") (pin "3") (pinfunction "3_3") (pintype "passive"))
      (node (ref "R40") (pin "2") (pinfunction "2_2") (pintype "passive"))
    )
    (net (code "98") (name "Net-(JP13-Pad1)") (class "Default")
      (node (ref "JP13") (pin "1") (pinfunction "1_1") (pintype "passive"))
      (node (ref "JP3") (pin "1") (pinfunction "1_1") (pintype "passive"))
      (node (ref "R44") (pin "2") (pinfunction "2_2") (pintype "passive"))
      (node (ref "R53") (pin "2") (pinfunction "2_2") (pintype "passive"))
      (node (ref "RN4") (pin "1") (pinfunction "1_1") (pintype "passive"))
      (node (ref "RN5") (pin "9") (pinfunction "9_9") (pintype "passive"))
    )
    (net (code "99") (name "Net-(JP14-Pad1)") (class "Default")
      (node (ref "JP14") (pin "1") (pinfunction "1_1") (pintype "passive"))
      (node (ref "JP2") (pin "1") (pinfunction "1_1") (pintype "passive"))
      (node (ref "R35") (pin "2") (pinfunction "2_2") (pintype "passive"))
      (node (ref "R45") (pin "2") (pinfunction "2_2") (pintype "passive"))
      (node (ref "RN1") (pin "1") (pinfunction "1_1") (pintype "passive"))
      (node (ref "RN2") (pin "9") (pinfunction "9_9") (pintype "passive"))
    )
    (net (code "100") (name "Net-(Q1-G)") (class "Default")
      (node (ref "Q1") (pin "1") (pinfunction "G_1") (pintype "passive"))
      (node (ref "R3") (pin "2") (pinfunction "2_2") (pintype "passive"))
    )
    (net (code "101") (name "Net-(Q2-G)") (class "Default")
      (node (ref "Q2") (pin "1") (pinfunction "G_1") (pintype "passive"))
      (node (ref "R4") (pin "2") (pinfunction "2_2") (pintype "passive"))
    )
    (net (code "102") (name "Net-(Q3-G)") (class "Default")
      (node (ref "Q3") (pin "1") (pinfunction "G_1") (pintype "passive"))
      (node (ref "R5") (pin "2") (pinfunction "2_2") (pintype "passive"))
    )
    (net (code "103") (name "Net-(Q4-G)") (class "Default")
      (node (ref "Q4") (pin "1") (pinfunction "G_1") (pintype "passive"))
      (node (ref "R6") (pin "2") (pinfunction "2_2") (pintype "passive"))
    )
    (net (code "104") (name "Net-(Q5-G)") (class "Default")
      (node (ref "Q5") (pin "1") (pinfunction "G_1") (pintype "passive"))
      (node (ref "R7") (pin "2") (pinfunction "2_2") (pintype "passive"))
    )
    (net (code "105") (name "Net-(Q6-G)") (class "Default")
      (node (ref "Q6") (pin "1") (pinfunction "G_1") (pintype "passive"))
      (node (ref "R8") (pin "2") (pinfunction "2_2") (pintype "passive"))
    )
    (net (code "106") (name "Net-(Q7-G)") (class "Default")
      (node (ref "Q7") (pin "1") (pinfunction "G_1") (pintype "passive"))
      (node (ref "R9") (pin "2") (pinfunction "2_2") (pintype "passive"))
    )
    (net (code "107") (name "Net-(Q8-G)") (class "Default")
      (node (ref "Q8") (pin "1") (pinfunction "G_1") (pintype "passive"))
      (node (ref "R10") (pin "2") (pinfunction "2_2") (pintype "passive"))
    )
    (net (code "108") (name "Net-(Q9-G)") (class "Default")
      (node (ref "Q9") (pin "1") (pinfunction "G_1") (pintype "passive"))
      (node (ref "R11") (pin "2") (pinfunction "2_2") (pintype "passive"))
    )
    (net (code "109") (name "Net-(Q10-G)") (class "Default")
      (node (ref "Q10") (pin "1") (pinfunction "G_1") (pintype "passive"))
      (node (ref "R12") (pin "2") (pinfunction "2_2") (pintype "passive"))
    )
    (net (code "110") (name "Net-(Q11-G)") (class "Default")
      (node (ref "Q11") (pin "1") (pinfunction "G_1") (pintype "passive"))
      (node (ref "R13") (pin "2") (pinfunction "2_2") (pintype "passive"))
    )
    (net (code "111") (name "Net-(Q12-G)") (class "Default")
      (node (ref "Q12") (pin "1") (pinfunction "G_1") (pintype "passive"))
      (node (ref "R14") (pin "2") (pinfunction "2_2") (pintype "passive"))
    )
    (net (code "112") (name "Net-(Q13-G)") (class "Default")
      (node (ref "Q13") (pin "1") (pinfunction "G_1") (pintype "passive"))
      (node (ref "R15") (pin "2") (pinfunction "2_2") (pintype "passive"))
    )
    (net (code "113") (name "Net-(Q14-G)") (class "Default")
      (node (ref "Q14") (pin "1") (pinfunction "G_1") (pintype "passive"))
      (node (ref "R16") (pin "2") (pinfunction "2_2") (pintype "passive"))
    )
    (net (code "114") (name "Net-(Q15-G)") (class "Default")
      (node (ref "Q15") (pin "1") (pinfunction "G_1") (pintype "passive"))
      (node (ref "R17") (pin "2") (pinfunction "2_2") (pintype "passive"))
    )
    (net (code "115") (name "Net-(Q16-G)") (class "Default")
      (node (ref "Q16") (pin "1") (pinfunction "G_1") (pintype "passive"))
      (node (ref "R18") (pin "2") (pinfunction "2_2") (pintype "passive"))
    )
    (net (code "116") (name "Net-(RN1B-1)") (class "Default")
      (node (ref "JP14") (pin "2") (pinfunction "2_2") (pintype "passive"))
      (node (ref "JP2") (pin "2") (pinfunction "2_2") (pintype "passive"))
      (node (ref "R34") (pin "2") (pinfunction "2_2") (pintype "passive"))
      (node (ref "R46") (pin "1") (pinfunction "1_1") (pintype "passive"))
      (node (ref "RN1") (pin "2") (pinfunction "1_2") (pintype "passive"))
      (node (ref "RN2") (pin "8") (pinfunction "8_8") (pintype "passive"))
    )
    (net (code "117") (name "Net-(RN1C-1)") (class "Default")
      (node (ref "JP14") (pin "3") (pinfunction "3_3") (pintype "passive"))
      (node (ref "JP2") (pin "3") (pinfunction "3_3") (pintype "passive"))
      (node (ref "R33") (pin "2") (pinfunction "2_2") (pintype "passive"))
      (node (ref "R47") (pin "1") (pinfunction "1_1") (pintype "passive"))
      (node (ref "RN1") (pin "3") (pinfunction "1_3") (pintype "passive"))
      (node (ref "RN2") (pin "7") (pinfunction "7_7") (pintype "passive"))
    )
    (net (code "118") (name "Net-(RN1D-1)") (class "Default")
      (node (ref "JP14") (pin "4") (pinfunction "4_4") (pintype "passive"))
      (node (ref "JP2") (pin "4") (pinfunction "4_4") (pintype "passive"))
      (node (ref "R32") (pin "2") (pinfunction "2_2") (pintype "passive"))
      (node (ref "R48") (pin "1") (pinfunction "1_1") (pintype "passive"))
      (node (ref "RN1") (pin "4") (pinfunction "1_4") (pintype "passive"))
      (node (ref "RN2") (pin "6") (pinfunction "6_6") (pintype "passive"))
    )
    (net (code "119") (name "Net-(RN1E-1)") (class "Default")
      (node (ref "JP14") (pin "7") (pinfunction "7_7") (pintype "passive"))
      (node (ref "JP2") (pin "5") (pinfunction "5_5") (pintype "passive"))
      (node (ref "R31") (pin "2") (pinfunction "2_2") (pintype "passive"))
      (node (ref "R49") (pin "1") (pinfunction "1_1") (pintype "passive"))
      (node (ref "RN1") (pin "5") (pinfunction "1_5") (pintype "passive"))
      (node (ref "RN2") (pin "5") (pinfunction "5_5") (pintype "passive"))
    )
    (net (code "120") (name "Net-(RN1F-1)") (class "Default")
      (node (ref "JP14") (pin "8") (pinfunction "8_8") (pintype "passive"))
      (node (ref "JP2") (pin "6") (pinfunction "6_6") (pintype "passive"))
      (node (ref "R30") (pin "2") (pinfunction "2_2") (pintype "passive"))
      (node (ref "R50") (pin "1") (pinfunction "1_1") (pintype "passive"))
      (node (ref "RN1") (pin "6") (pinfunction "1_6") (pintype "passive"))
      (node (ref "RN2") (pin "4") (pinfunction "4_4") (pintype "passive"))
    )
    (net (code "121") (name "Net-(RN1G-1)") (class "Default")
      (node (ref "JP14") (pin "9") (pinfunction "9_9") (pintype "passive"))
      (node (ref "JP2") (pin "7") (pinfunction "7_7") (pintype "passive"))
      (node (ref "R29") (pin "2") (pinfunction "2_2") (pintype "passive"))
      (node (ref "R51") (pin "1") (pinfunction "1_1") (pintype "passive"))
      (node (ref "RN1") (pin "7") (pinfunction "1_7") (pintype "passive"))
      (node (ref "RN2") (pin "3") (pinfunction "3_3") (pintype "passive"))
    )
    (net (code "122") (name "Net-(RN1H-1)") (class "Default")
      (node (ref "JP14") (pin "10") (pinfunction "10_10") (pintype "passive"))
      (node (ref "JP2") (pin "8") (pinfunction "8_8") (pintype "passive"))
      (node (ref "R28") (pin "2") (pinfunction "2_2") (pintype "passive"))
      (node (ref "R52") (pin "1") (pinfunction "1_1") (pintype "passive"))
      (node (ref "RN1") (pin "8") (pinfunction "1_8") (pintype "passive"))
      (node (ref "RN2") (pin "2") (pinfunction "2_2") (pintype "passive"))
    )
    (net (code "123") (name "Net-(RN4B-1)") (class "Default")
      (node (ref "JP13") (pin "2") (pinfunction "2_2") (pintype "passive"))
      (node (ref "JP3") (pin "2") (pinfunction "2_2") (pintype "passive"))
      (node (ref "R43") (pin "2") (pinfunction "2_2") (pintype "passive"))
      (node (ref "R54") (pin "2") (pinfunction "2_2") (pintype "passive"))
      (node (ref "RN4") (pin "2") (pinfunction "1_2") (pintype "passive"))
      (node (ref "RN5") (pin "8") (pinfunction "8_8") (pintype "passive"))
    )
    (net (code "124") (name "Net-(RN4C-1)") (class "Default")
      (node (ref "JP13") (pin "3") (pinfunction "3_3") (pintype "passive"))
      (node (ref "JP3") (pin "3") (pinfunction "3_3") (pintype "passive"))
      (node (ref "R42") (pin "2") (pinfunction "2_2") (pintype "passive"))
      (node (ref "R55") (pin "2") (pinfunction "2_2") (pintype "passive"))
      (node (ref "RN4") (pin "3") (pinfunction "1_3") (pintype "passive"))
      (node (ref "RN5") (pin "7") (pinfunction "7_7") (pintype "passive"))
    )
    (net (code "125") (name "Net-(RN4D-1)") (class "Default")
      (node (ref "JP13") (pin "4") (pinfunction "4_4") (pintype "passive"))
      (node (ref "JP3") (pin "4") (pinfunction "4_4") (pintype "passive"))
      (node (ref "R41") (pin "2") (pinfunction "2_2") (pintype "passive"))
      (node (ref "R56") (pin "2") (pinfunction "2_2") (pintype "passive"))
      (node (ref "RN4") (pin "4") (pinfunction "1_4") (pintype "passive"))
      (node (ref "RN5") (pin "6") (pinfunction "6_6") (pintype "passive"))
    )
    (net (code "126") (name "Net-(RN4E-1)") (class "Default")
      (node (ref "JP13") (pin "7") (pinfunction "7_7") (pintype "passive"))
      (node (ref "JP3") (pin "5") (pinfunction "5_5") (pintype "passive"))
      (node (ref "R39") (pin "2") (pinfunction "2_2") (pintype "passive"))
      (node (ref "R57") (pin "2") (pinfunction "2_2") (pintype "passive"))
      (node (ref "RN4") (pin "5") (pinfunction "1_5") (pintype "passive"))
      (node (ref "RN5") (pin "5") (pinfunction "5_5") (pintype "passive"))
    )
    (net (code "127") (name "Net-(RN4F-1)") (class "Default")
      (node (ref "JP13") (pin "8") (pinfunction "8_8") (pintype "passive"))
      (node (ref "JP3") (pin "6") (pinfunction "6_6") (pintype "passive"))
      (node (ref "R38") (pin "2") (pinfunction "2_2") (pintype "passive"))
      (node (ref "R58") (pin "2") (pinfunction "2_2") (pintype "passive"))
      (node (ref "RN4") (pin "6") (pinfunction "1_6") (pintype "passive"))
      (node (ref "RN5") (pin "4") (pinfunction "4_4") (pintype "passive"))
    )
    (net (code "128") (name "Net-(RN4G-1)") (class "Default")
      (node (ref "JP13") (pin "9") (pinfunction "9_9") (pintype "passive"))
      (node (ref "JP3") (pin "7") (pinfunction "7_7") (pintype "passive"))
      (node (ref "R37") (pin "2") (pinfunction "2_2") (pintype "passive"))
      (node (ref "R59") (pin "2") (pinfunction "2_2") (pintype "passive"))
      (node (ref "RN4") (pin "7") (pinfunction "1_7") (pintype "passive"))
      (node (ref "RN5") (pin "3") (pinfunction "3_3") (pintype "passive"))
    )
    (net (code "129") (name "Net-(RN4H-1)") (class "Default")
      (node (ref "JP13") (pin "10") (pinfunction "10_10") (pintype "passive"))
      (node (ref "JP3") (pin "8") (pinfunction "8_8") (pintype "passive"))
      (node (ref "R36") (pin "2") (pinfunction "2_2") (pintype "passive"))
      (node (ref "R60") (pin "2") (pinfunction "2_2") (pintype "passive"))
      (node (ref "RN4") (pin "8") (pinfunction "1_8") (pintype "passive"))
      (node (ref "RN5") (pin "2") (pinfunction "2_2") (pintype "passive"))
    )
    (net (code "130") (name "Net-(SJ13-1)") (class "Default")
      (node (ref "SJ13") (pin "P$1") (pinfunction "1_P$1") (pintype "passive"))
      (node (ref "U$1") (pin "PB14") (pinfunction "PB14_PB14") (pintype "bidirectional"))
    )
    (net (code "131") (name "Net-(SJ14-1)") (class "Default")
      (node (ref "SJ14") (pin "P$1") (pinfunction "1_P$1") (pintype "passive"))
      (node (ref "U$1") (pin "VIN2") (pinfunction "VIN2_VIN2") (pintype "power_in"))
    )
    (net (code "132") (name "Net-(SJ16-2)") (class "Default")
      (node (ref "JP9") (pin "2") (pinfunction "2_2") (pintype "passive"))
      (node (ref "SJ15") (pin "2") (pinfunction "2_2") (pintype "passive"))
      (node (ref "SJ16") (pin "P$2") (pinfunction "2_P$2") (pintype "passive"))
    )
    (net (code "133") (name "OLAT") (class "Default")
      (node (ref "IC3") (pin "12") (pinfunction "RCK_12") (pintype "input"))
      (node (ref "IC5") (pin "12") (pinfunction "RCK_12") (pintype "input"))
      (node (ref "R21") (pin "1") (pinfunction "1_1") (pintype "passive"))
      (node (ref "U$1") (pin "PA8") (pinfunction "PA8_PA8") (pintype "bidirectional"))
    )
    (net (code "134") (name "SCK") (class "Default")
      (node (ref "IC3") (pin "11") (pinfunction "SCK_11") (pintype "input"))
      (node (ref "IC5") (pin "11") (pinfunction "SCK_11") (pintype "input"))
      (node (ref "JP9") (pin "3") (pinfunction "3_3") (pintype "passive"))
      (node (ref "R19") (pin "1") (pinfunction "1_1") (pintype "passive"))
      (node (ref "U$1") (pin "PB3") (pinfunction "PB3_PB3") (pintype "bidirectional"))
    )
    (net (code "135") (name "SCK2") (class "Default")
      (node (ref "IC1") (pin "7") (pinfunction "CLK_7") (pintype "input"))
      (node (ref "IC4") (pin "7") (pinfunction "CLK_7") (pintype "input"))
      (node (ref "U$1") (pin "PB10") (pinfunction "PB10_PB10") (pintype "bidirectional"))
    )
    (net (code "136") (name "SLNK1") (class "Default")
      (node (ref "IC3") (pin "14") (pinfunction "SER_14") (pintype "input"))
      (node (ref "IC5") (pin "9") (pinfunction "QH*_9") (pintype "tri_state"))
      (node (ref "SJ17") (pin "P$1") (pinfunction "1_P$1") (pintype "passive"))
    )
    (net (code "137") (name "SLNK2") (class "Default")
      (node (ref "IC3") (pin "9") (pinfunction "QH*_9") (pintype "tri_state"))
      (node (ref "SJ16") (pin "P$1") (pinfunction "1_P$1") (pintype "passive"))
    )
    (net (code "138") (name "SLNK3") (class "Default")
      (node (ref "IC1") (pin "13") (pinfunction "QH_13") (pintype "output"))
      (node (ref "IC4") (pin "1") (pinfunction "SER_1") (pintype "input"))
    )
    (net (code "139") (name "SRV1") (class "Default")
      (node (ref "JP7") (pin "2") (pinfunction "2_2") (pintype "passive"))
      (node (ref "R25") (pin "2") (pinfunction "2_2") (pintype "passive"))
      (node (ref "U$1") (pin "PC9") (pinfunction "PC9_PC9") (pintype "bidirectional"))
    )
    (net (code "140") (name "SRV2") (class "Default")
      (node (ref "JP7") (pin "1") (pinfunction "1_1") (pintype "passive"))
      (node (ref "R24") (pin "2") (pinfunction "2_2") (pintype "passive"))
      (node (ref "U$1") (pin "PC7") (pinfunction "PC7_PC7") (pintype "bidirectional"))
    )
    (net (code "141") (name "SRV3") (class "Default")
      (node (ref "JP11") (pin "2") (pinfunction "2_2") (pintype "passive"))
      (node (ref "R26") (pin "2") (pinfunction "2_2") (pintype "passive"))
      (node (ref "U$1") (pin "PC8") (pinfunction "PC8_PC8") (pintype "bidirectional"))
    )
    (net (code "142") (name "SRV4") (class "Default")
      (node (ref "JP11") (pin "1") (pinfunction "1_1") (pintype "passive"))
      (node (ref "R27") (pin "2") (pinfunction "2_2") (pintype "passive"))
      (node (ref "U$1") (pin "PC6") (pinfunction "PC6_PC6") (pintype "bidirectional"))
    )
    (net (code "143") (name "SRV5") (class "Default")
      (node (ref "JP12") (pin "2") (pinfunction "2_2") (pintype "passive"))
      (node (ref "R64") (pin "2") (pinfunction "2_2") (pintype "passive"))
      (node (ref "U$1") (pin "PF1-PH1") (pinfunction "PF1-PH1_PF1-PH1") (pintype "bidirectional"))
    )
    (net (code "144") (name "SRV6") (class "Default")
      (node (ref "JP12") (pin "1") (pinfunction "1_1") (pintype "passive"))
      (node (ref "R65") (pin "2") (pinfunction "2_2") (pintype "passive"))
      (node (ref "U$1") (pin "PA15") (pinfunction "PA15_PA15") (pintype "bidirectional"))
    )
    (net (code "145") (name "SRV7") (class "Default")
      (node (ref "JP16") (pin "2") (pinfunction "2_2") (pintype "passive"))
      (node (ref "R66") (pin "2") (pinfunction "2_2") (pintype "passive"))
      (node (ref "U$1") (pin "PC12") (pinfunction "PC12_PC12") (pintype "bidirectional"))
    )
    (net (code "146") (name "SRV8") (class "Default")
      (node (ref "JP16") (pin "1") (pinfunction "1_1") (pintype "passive"))
      (node (ref "R67") (pin "2") (pinfunction "2_2") (pintype "passive"))
      (node (ref "U$1") (pin "PD2") (pinfunction "PD2_PD2") (pintype "bidirectional"))
    )
    (net (code "147") (name "TIN3") (class "Default")
      (node (ref "IC9") (pin "10") (pinfunction "+IN_10") (pintype "input"))
      (node (ref "U$1") (pin "PB15") (pinfunction "PB15_PB15") (pintype "bidirectional"))
      (node (ref "U$2") (pin "4") (pinfunction "I_4") (pintype "input"))
    )
    (net (code "148") (name "TIN4") (class "Default")
      (node (ref "IC9") (pin "12") (pinfunction "+IN_12") (pintype "input"))
      (node (ref "U$1") (pin "PB12") (pinfunction "PB12_PB12") (pintype "bidirectional"))
      (node (ref "U$3") (pin "2") (pinfunction "I_2") (pintype "input"))
    )
    (net (code "149") (name "V+") (class "Default")
      (node (ref "AP1509") (pin "3") (pinfunction "FB_3") (pintype "bidirectional"))
      (node (ref "C1") (pin "1") (pinfunction "1_1") (pintype "passive"))
      (node (ref "C2") (pin "+") (pinfunction "+_+") (pintype "passive"))
      (node (ref "IC10") (pin "1") (pinfunction "FB_1") (pintype "input"))
      (node (ref "L1") (pin "1") (pinfunction "1_1") (pintype "passive"))
      (node (ref "U$1") (pin "E5V") (pinfunction "E5V_E5V") (pintype "power_in"))
    )
    (net (code "150") (name "unconnected-(H1-MOUNT-PadB3,3)") (class "Default")
      (node (ref "H1") (pin "B3,3") (pinfunction "MOUNT_B3,3") (pintype "passive"))
    )
    (net (code "151") (name "unconnected-(H2-MOUNT-PadB3,3)") (class "Default")
      (node (ref "H2") (pin "B3,3") (pinfunction "MOUNT_B3,3") (pintype "passive"))
    )
    (net (code "152") (name "unconnected-(H3-MOUNT-PadB3,3)") (class "Default")
      (node (ref "H3") (pin "B3,3") (pinfunction "MOUNT_B3,3") (pintype "passive"))
    )
    (net (code "153") (name "unconnected-(H4-MOUNT-PadB3,3)") (class "Default")
      (node (ref "H4") (pin "B3,3") (pinfunction "MOUNT_B3,3") (pintype "passive"))
    )
    (net (code "154") (name "unconnected-(J3-Pad2)") (class "Default")
      (node (ref "J3") (pin "2") (pinfunction "2_2") (pintype "passive"))
    )
    (net (code "155") (name "unconnected-(U$1-PadBOOT0)") (class "Default")
      (node (ref "U$1") (pin "BOOT0") (pinfunction "BOOT0_BOOT0") (pintype "bidirectional"))
    )
    (net (code "156") (name "unconnected-(U$1-PadIOREF2)") (class "Default")
      (node (ref "U$1") (pin "IOREF2") (pinfunction "IOREF2_IOREF2") (pintype "input"))
    )
    (net (code "157") (name "unconnected-(U$1-PadNC1-PF7)") (class "Default")
      (node (ref "U$1") (pin "NC1-PF7") (pinfunction "NC1-PF7_NC1-PF7") (pintype "bidirectional"))
    )
    (net (code "158") (name "unconnected-(U$1-PadNC2-PF6)") (class "Default")
      (node (ref "U$1") (pin "NC2-PF6") (pinfunction "NC2-PF6_NC2-PF6") (pintype "bidirectional"))
    )
    (net (code "159") (name "unconnected-(U$1-PadNC3)") (class "Default")
      (node (ref "U$1") (pin "NC3") (pinfunction "NC3_NC3") (pintype "no_connect"))
    )
    (net (code "160") (name "unconnected-(U$1-PadNC4)") (class "Default")
      (node (ref "U$1") (pin "NC4") (pinfunction "NC4_NC4") (pintype "no_connect"))
    )
    (net (code "161") (name "unconnected-(U$1-PadNC5-PD8)") (class "Default")
      (node (ref "U$1") (pin "NC5-PD8") (pinfunction "NC5-PD8_NC5-PD8") (pintype "bidirectional"))
    )
    (net (code "162") (name "unconnected-(U$1-PadNC6-PB11)") (class "Default")
      (node (ref "U$1") (pin "NC6-PB11") (pinfunction "NC6-PB11_NC6-PB11") (pintype "no_connect"))
    )
    (net (code "163") (name "unconnected-(U$1-PadNC7-PF5)") (class "Default")
      (node (ref "U$1") (pin "NC7-PF5") (pinfunction "NC7-PF5_NC7-PF5") (pintype "bidirectional"))
    )
    (net (code "164") (name "unconnected-(U$1-PadNC8-PF4)") (class "Default")
      (node (ref "U$1") (pin "NC8-PF4") (pinfunction "NC8-PF4_NC8-PF4") (pintype "bidirectional"))
    )
    (net (code "165") (name "unconnected-(U$1-PadNRESET)") (class "Default")
      (node (ref "U$1") (pin "NRESET") (pinfunction "NRESET_NRESET") (pintype "input"))
    )
    (net (code "166") (name "unconnected-(U$1-PadPA1)") (class "Default")
      (node (ref "U$1") (pin "PA1") (pinfunction "PA1_PA1") (pintype "bidirectional"))
    )
    (net (code "167") (name "unconnected-(U$1-PadPA2)") (class "Default")
      (node (ref "U$1") (pin "PA2") (pinfunction "PA2_PA2") (pintype "bidirectional"))
    )
    (net (code "168") (name "unconnected-(U$1-PadPA3)") (class "Default")
      (node (ref "U$1") (pin "PA3") (pinfunction "PA3_PA3") (pintype "bidirectional"))
    )
    (net (code "169") (name "unconnected-(U$1-PadPA5)") (class "Default")
      (node (ref "U$1") (pin "PA5") (pinfunction "PA5_PA5") (pintype "bidirectional"))
    )
    (net (code "170") (name "unconnected-(U$1-PadPA7)") (class "Default")
      (node (ref "U$1") (pin "PA7") (pinfunction "PA7_PA7") (pintype "bidirectional"))
    )
    (net (code "171") (name "unconnected-(U$1-PadPA9)") (class "Default")
      (node (ref "U$1") (pin "PA9") (pinfunction "PA9_PA9") (pintype "bidirectional"))
    )
    (net (code "172") (name "unconnected-(U$1-PadPA10)") (class "Default")
      (node (ref "U$1") (pin "PA10") (pinfunction "PA10_PA10") (pintype "bidirectional"))
    )
    (net (code "173") (name "unconnected-(U$1-PadPA11)") (class "Default")
      (node (ref "U$1") (pin "PA11") (pinfunction "PA11_PA11") (pintype "bidirectional"))
    )
    (net (code "174") (name "unconnected-(U$1-PadPA12)") (class "Default")
      (node (ref "U$1") (pin "PA12") (pinfunction "PA12_PA12") (pintype "bidirectional"))
    )
    (net (code "175") (name "unconnected-(U$1-PadPA13)") (class "Default")
      (node (ref "U$1") (pin "PA13") (pinfunction "PA13_PA13") (pintype "bidirectional"))
    )
    (net (code "176") (name "unconnected-(U$1-PadPA14)") (class "Default")
      (node (ref "U$1") (pin "PA14") (pinfunction "PA14_PA14") (pintype "bidirectional"))
    )
    (net (code "177") (name "unconnected-(U$1-PadPB0)") (class "Default")
      (node (ref "U$1") (pin "PB0") (pinfunction "PB0_PB0") (pintype "bidirectional"))
    )
    (net (code "178") (name "unconnected-(U$1-PadPB13)") (class "Default")
      (node (ref "U$1") (pin "PB13") (pinfunction "PB13_PB13") (pintype "bidirectional"))
    )
    (net (code "179") (name "unconnected-(U$1-PadPC1)") (class "Default")
      (node (ref "U$1") (pin "PC1") (pinfunction "PC1_PC1") (pintype "bidirectional"))
    )
    (net (code "180") (name "unconnected-(U$1-PadPC4)") (class "Default")
      (node (ref "U$1") (pin "PC4") (pinfunction "PC4_PC4") (pintype "bidirectional"))
    )
    (net (code "181") (name "unconnected-(U$1-PadPC5)") (class "Default")
      (node (ref "U$1") (pin "PC5") (pinfunction "PC5_PC5") (pintype "bidirectional"))
    )
    (net (code "182") (name "unconnected-(U$1-PadPC13)") (class "Default")
      (node (ref "U$1") (pin "PC13") (pinfunction "PC13_PC13") (pintype "bidirectional"))
    )
    (net (code "183") (name "unconnected-(U$1-PadPC14)") (class "Default")
      (node (ref "U$1") (pin "PC14") (pinfunction "PC14_PC14") (pintype "bidirectional"))
    )
    (net (code "184") (name "unconnected-(U$1-PadPC15)") (class "Default")
      (node (ref "U$1") (pin "PC15") (pinfunction "PC15_PC15") (pintype "bidirectional"))
    )
    (net (code "185") (name "unconnected-(U$1-PadPF0-PH0)") (class "Default")
      (node (ref "U$1") (pin "PF0-PH0") (pinfunction "PF0-PH0_PF0-PH0") (pintype "bidirectional"))
    )
  )
)
